# PCIE.net
KiCad netlist of a schematic drawn in EasyEDA Pro
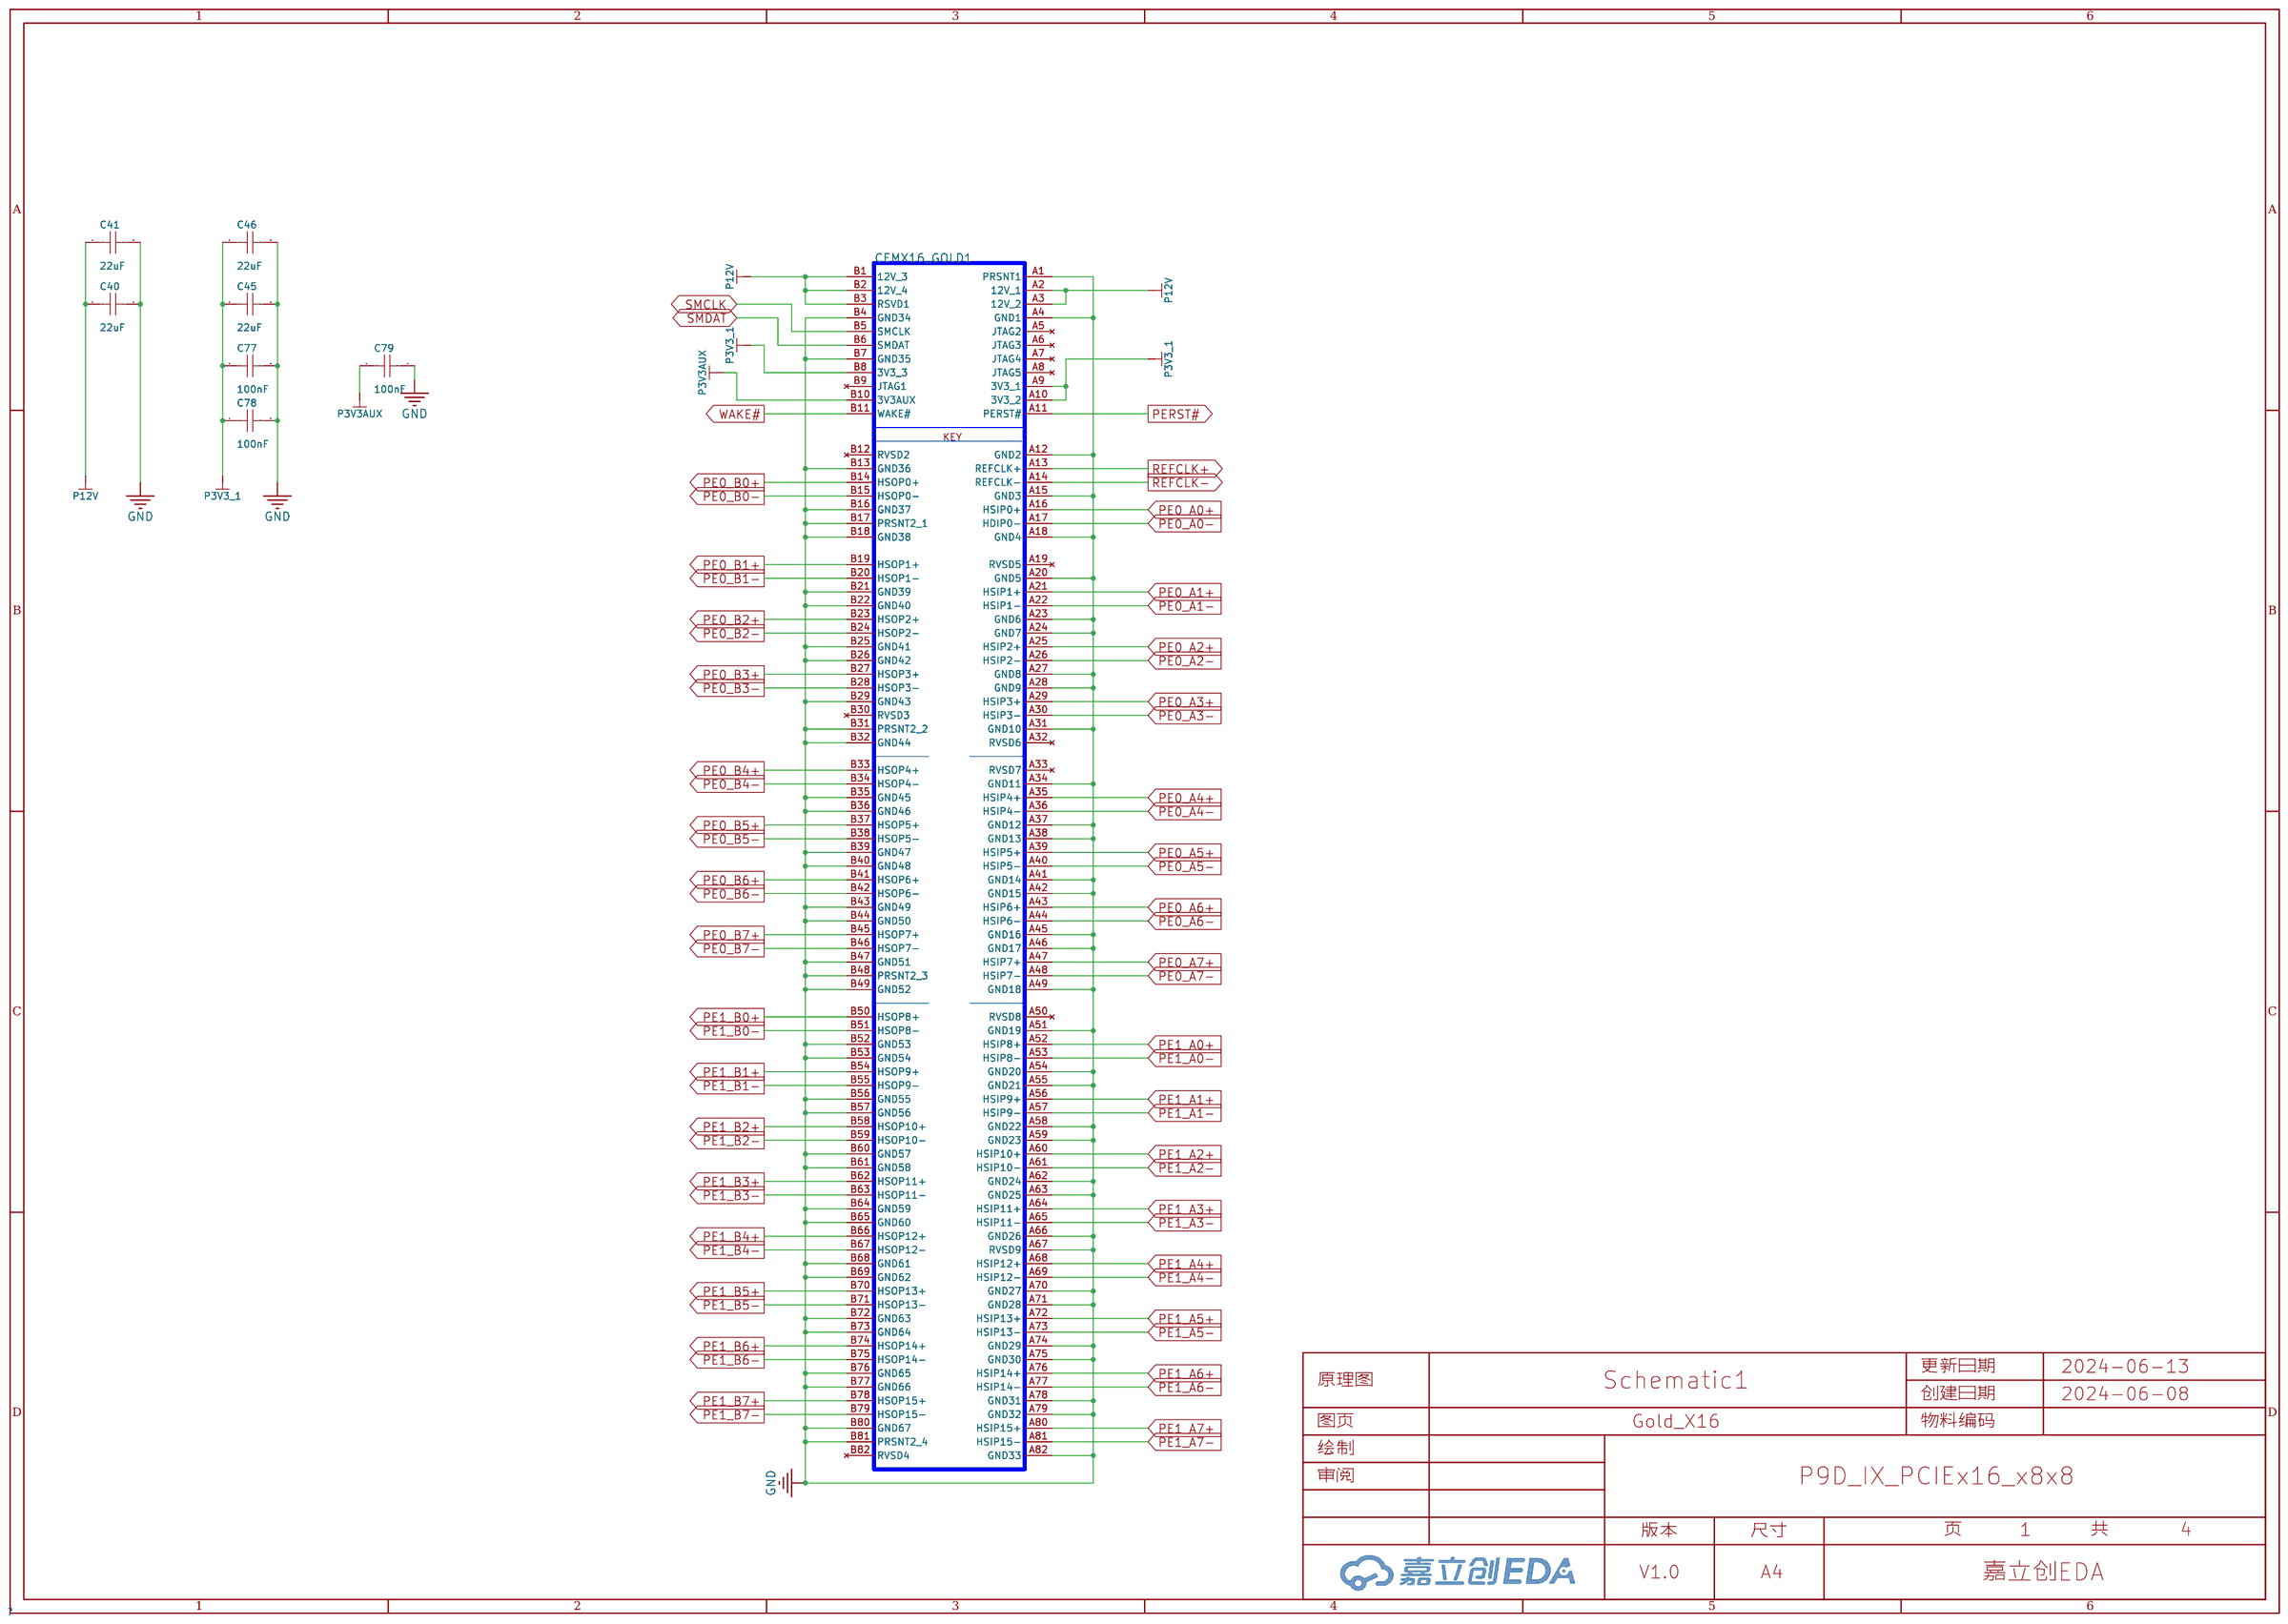
[diagram p0: Gold_X16]
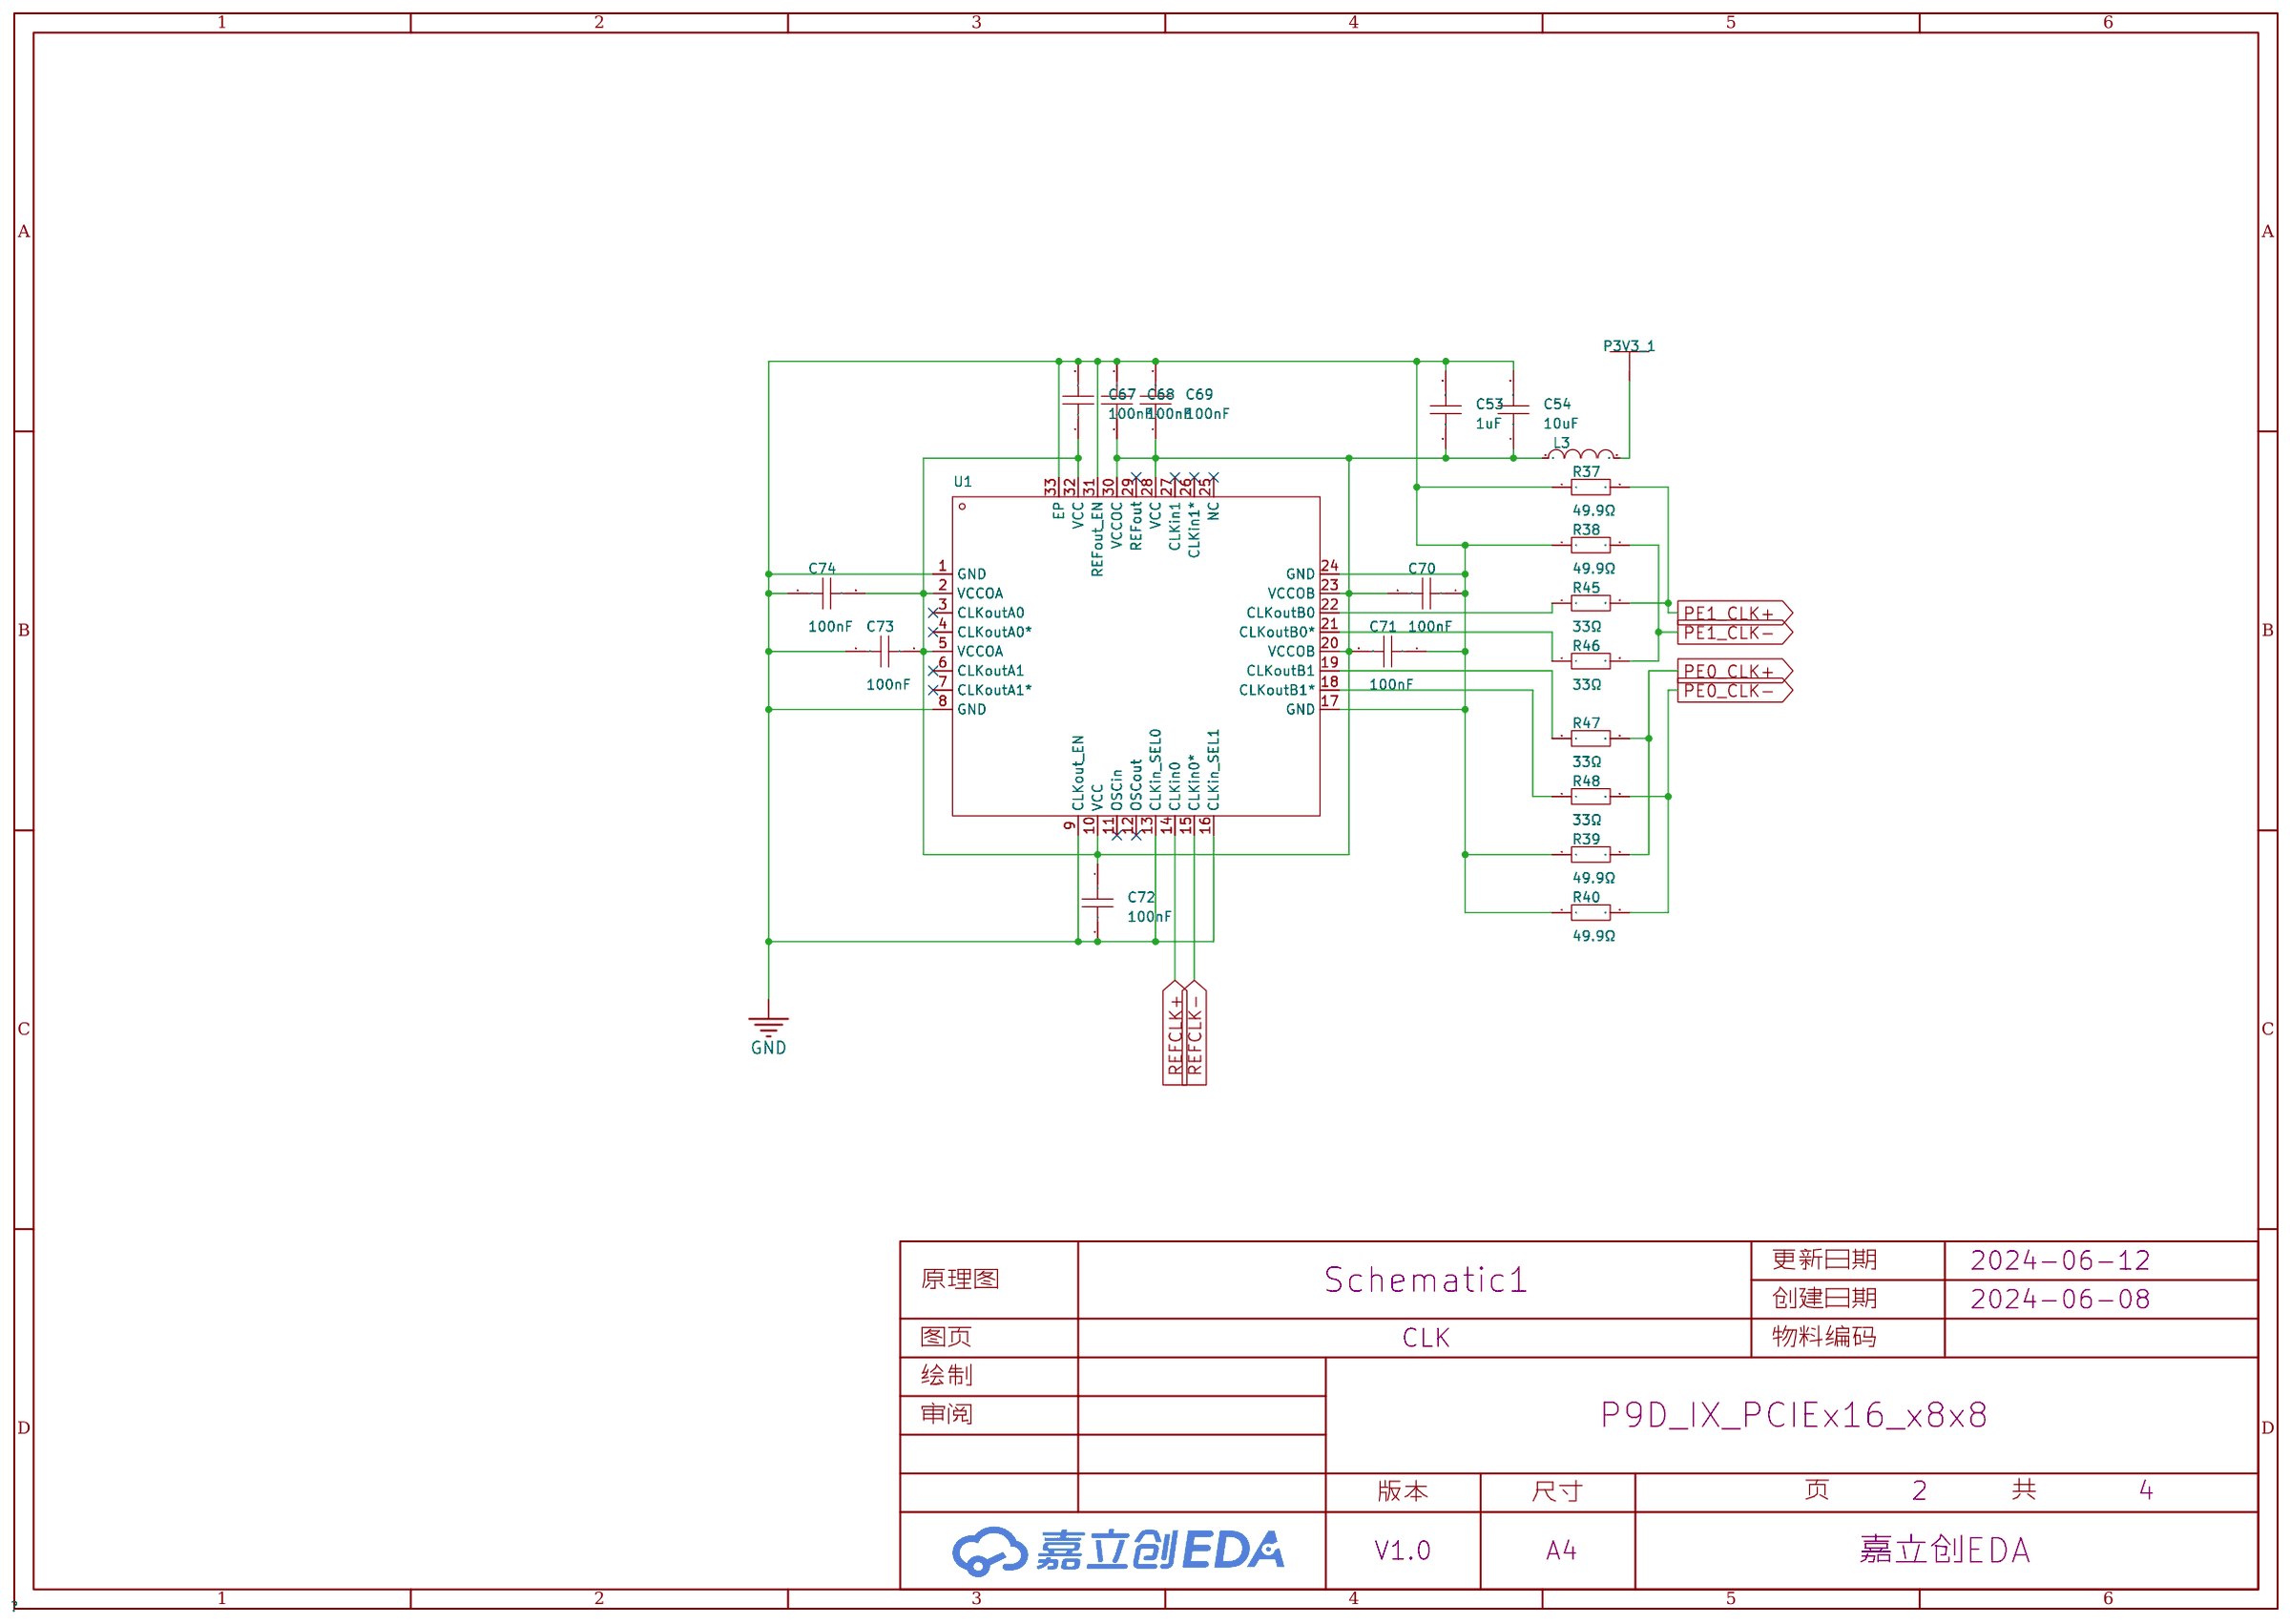
[diagram p1: CLK]
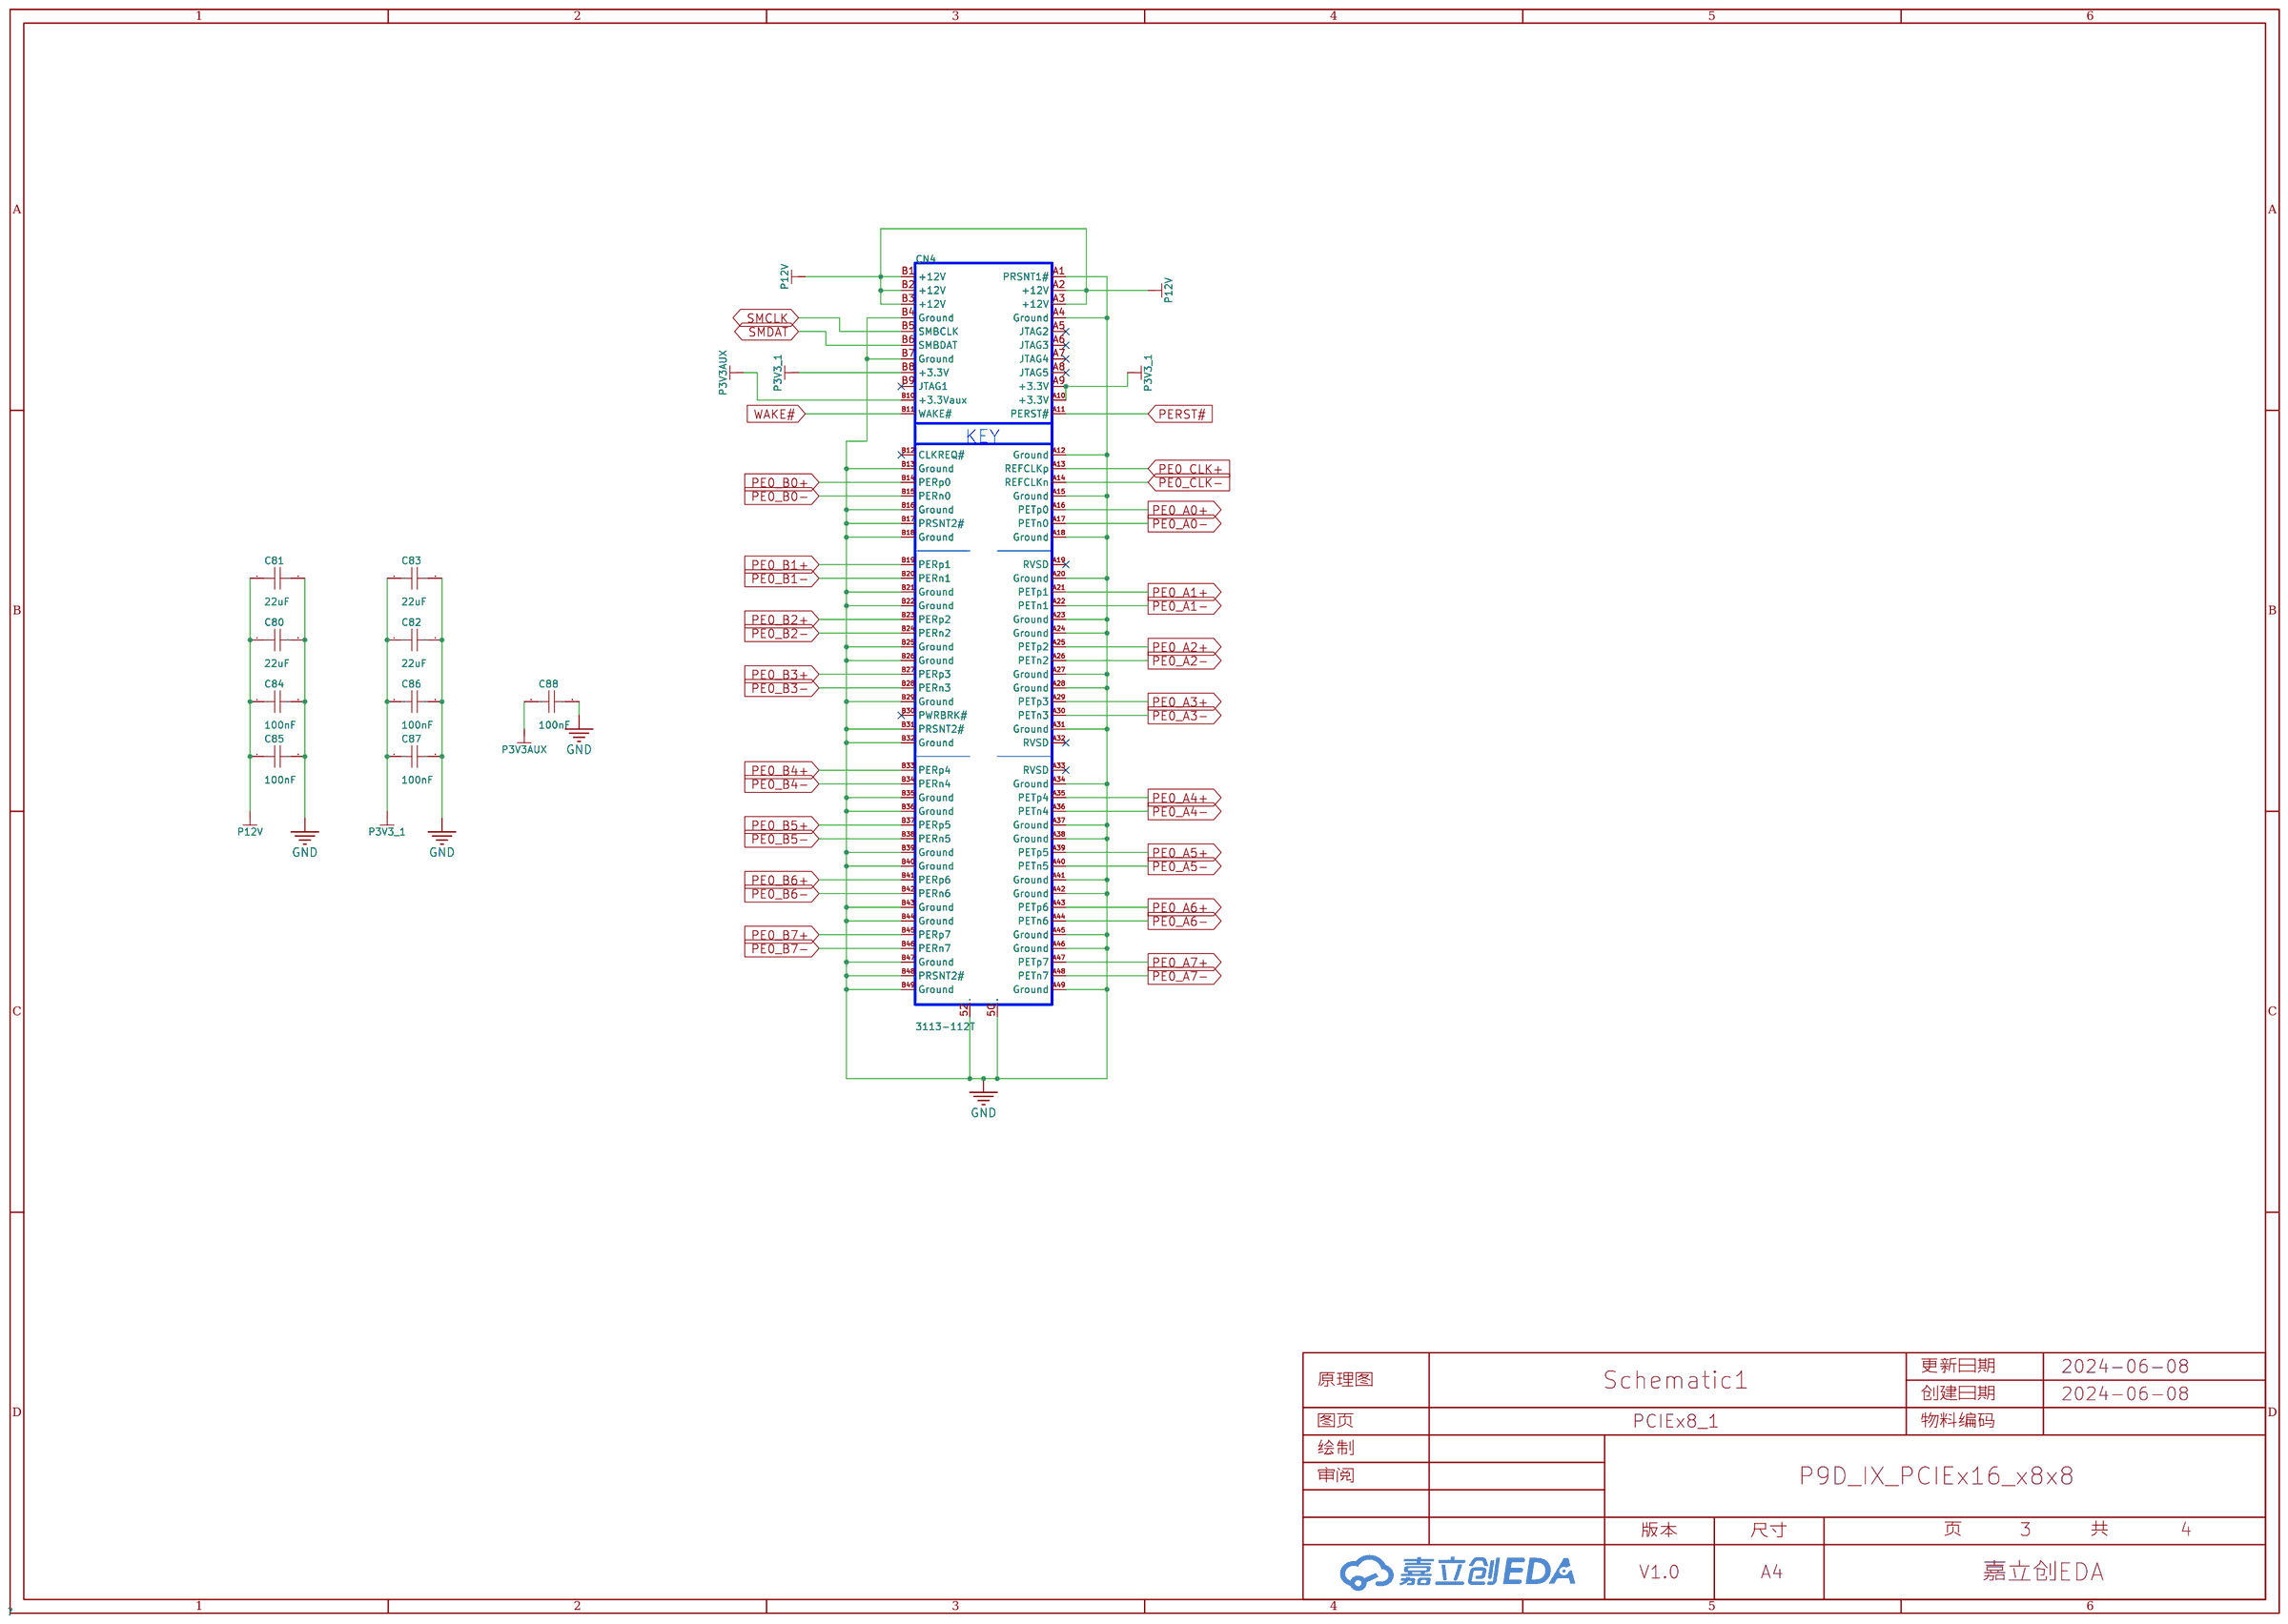
[diagram p2: PCIEx8_1]
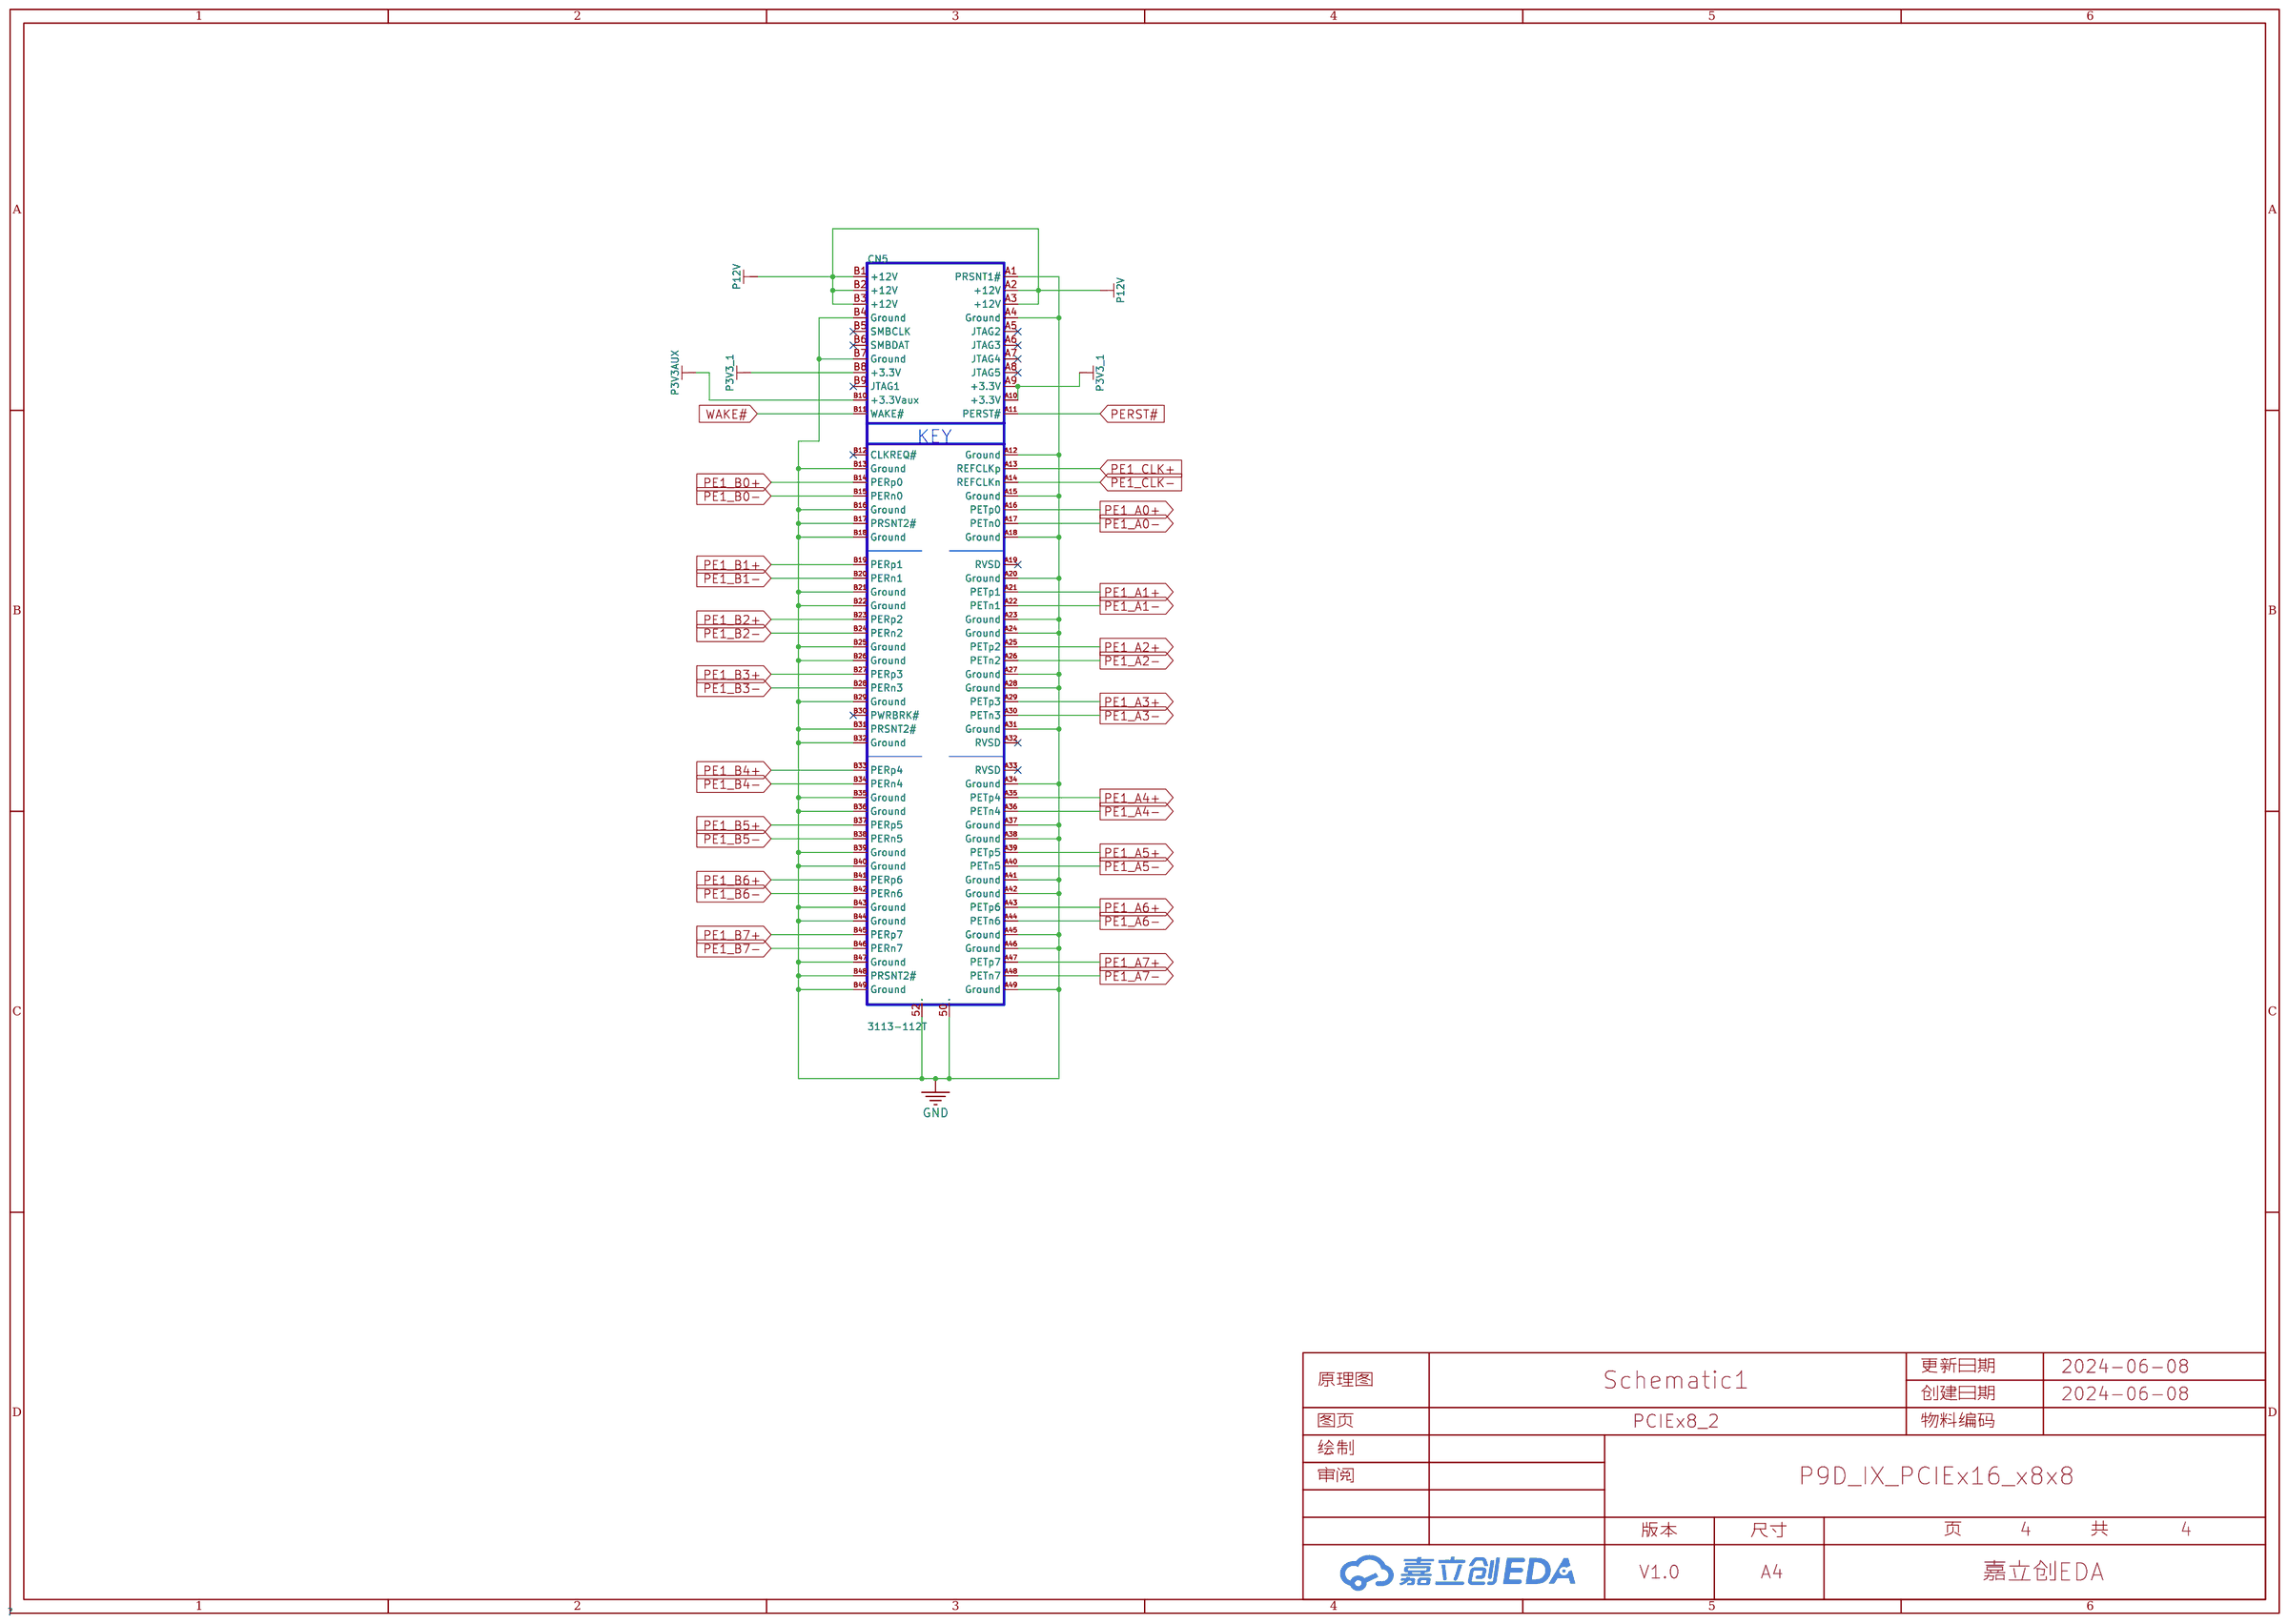
[diagram p3: PCIEx8_2]

(export (version "E")
  (design (tool "Eeschema 10.0.6"))
  (components
    (comp (ref "C40")
      (value "22uF")
      (footprint "easyedapro:C0402")
      (fields
        (field (name "Manufacturer Part") "CL21A226MAQNNNE")
        (field (name "Manufacturer") "SAMSUNG(三星)")
      )
      (libsource (lib "easyedapro") (part "CapAcitance"))
    )
    (comp (ref "C41")
      (value "22uF")
      (footprint "easyedapro:C0402")
      (fields
        (field (name "Manufacturer Part") "CL21A226MAQNNNE")
        (field (name "Manufacturer") "SAMSUNG(三星)")
      )
      (libsource (lib "easyedapro") (part "CapAcitance"))
    )
    (comp (ref "C45")
      (value "22uF")
      (footprint "easyedapro:C0402")
      (fields
        (field (name "Manufacturer Part") "CL21A226MAQNNNE")
        (field (name "Manufacturer") "SAMSUNG(三星)")
      )
      (libsource (lib "easyedapro") (part "CapAcitance"))
    )
    (comp (ref "C46")
      (value "22uF")
      (footprint "easyedapro:C0402")
      (fields
        (field (name "Manufacturer Part") "CL21A226MAQNNNE")
        (field (name "Manufacturer") "SAMSUNG(三星)")
      )
      (libsource (lib "easyedapro") (part "CapAcitance"))
    )
    (comp (ref "C77")
      (value "100nF")
      (footprint "easyedapro:C0402")
      (fields
        (field (name "Manufacturer Part") "CC0603KRX7R9BB104")
        (field (name "Manufacturer") "YAGEO(国巨)")
      )
      (libsource (lib "easyedapro") (part "CapAcitance"))
    )
    (comp (ref "C78")
      (value "100nF")
      (footprint "easyedapro:C0402")
      (fields
        (field (name "Manufacturer Part") "CC0603KRX7R9BB104")
        (field (name "Manufacturer") "YAGEO(国巨)")
      )
      (libsource (lib "easyedapro") (part "CapAcitance"))
    )
    (comp (ref "C79")
      (value "100nF")
      (footprint "easyedapro:C0402")
      (fields
        (field (name "Manufacturer Part") "CC0603KRX7R9BB104")
        (field (name "Manufacturer") "YAGEO(国巨)")
      )
      (libsource (lib "easyedapro") (part "CapAcitance"))
    )
    (comp (ref "CEMX16_GOLD1")
      (value "~")
      (footprint "easyedapro:PCIEX16_GOLD")
      (description "PCIEX16金手指")
      (libsource (lib "easyedapro") (part "PCIEX16金手指"))
    )
    (comp (ref "C53")
      (value "1uF")
      (footprint "easyedapro:C0402")
      (fields
        (field (name "Manufacturer Part") "CL10A105KB8NNNC")
        (field (name "Manufacturer") "SAMSUNG(三星)")
      )
      (libsource (lib "easyedapro") (part "CapAcitance"))
    )
    (comp (ref "C54")
      (value "10uF")
      (footprint "easyedapro:C0402")
      (fields
        (field (name "Manufacturer Part") "CL10A106KP8NNNC")
        (field (name "Manufacturer") "SAMSUNG(三星)")
      )
      (libsource (lib "easyedapro") (part "CapAcitance"))
    )
    (comp (ref "C67")
      (value "100nF")
      (footprint "easyedapro:C0402")
      (fields
        (field (name "Manufacturer Part") "CL05B104KO5NNNC")
        (field (name "Manufacturer") "SAMSUNG(三星)")
      )
      (libsource (lib "easyedapro") (part "CapAcitance"))
    )
    (comp (ref "C68")
      (value "100nF")
      (footprint "easyedapro:C0402")
      (fields
        (field (name "Manufacturer Part") "CL05B104KO5NNNC")
        (field (name "Manufacturer") "SAMSUNG(三星)")
      )
      (libsource (lib "easyedapro") (part "CapAcitance"))
    )
    (comp (ref "C69")
      (value "100nF")
      (footprint "easyedapro:C0402")
      (fields
        (field (name "Manufacturer Part") "CL05B104KO5NNNC")
        (field (name "Manufacturer") "SAMSUNG(三星)")
      )
      (libsource (lib "easyedapro") (part "CapAcitance"))
    )
    (comp (ref "C70")
      (value "100nF")
      (footprint "easyedapro:C0402")
      (fields
        (field (name "Manufacturer Part") "CL05B104KO5NNNC")
        (field (name "Manufacturer") "SAMSUNG(三星)")
      )
      (libsource (lib "easyedapro") (part "CapAcitance"))
    )
    (comp (ref "C71")
      (value "100nF")
      (footprint "easyedapro:C0402")
      (fields
        (field (name "Manufacturer Part") "CL05B104KO5NNNC")
        (field (name "Manufacturer") "SAMSUNG(三星)")
      )
      (libsource (lib "easyedapro") (part "CapAcitance"))
    )
    (comp (ref "C72")
      (value "100nF")
      (footprint "easyedapro:C0402")
      (fields
        (field (name "Manufacturer Part") "CL05B104KO5NNNC")
        (field (name "Manufacturer") "SAMSUNG(三星)")
      )
      (libsource (lib "easyedapro") (part "CapAcitance"))
    )
    (comp (ref "C73")
      (value "100nF")
      (footprint "easyedapro:C0402")
      (fields
        (field (name "Manufacturer Part") "CL05B104KO5NNNC")
        (field (name "Manufacturer") "SAMSUNG(三星)")
      )
      (libsource (lib "easyedapro") (part "CapAcitance"))
    )
    (comp (ref "C74")
      (value "100nF")
      (footprint "easyedapro:C0402")
      (fields
        (field (name "Manufacturer Part") "CL05B104KO5NNNC")
        (field (name "Manufacturer") "SAMSUNG(三星)")
      )
      (libsource (lib "easyedapro") (part "CapAcitance"))
    )
    (comp (ref "L3")
      (value "~")
      (footprint "easyedapro:L0805")
      (description "标称阻抗@测试频率:80Ω@100MHz;误差:±25%;直流电阻(RDC):0.04Ω;额定电流:3000mA;电路数:1;")
      (fields
        (field (name "Manufacturer Part") "PZ2012D800-3R0TF")
        (field (name "Manufacturer") "Sunlord(顺络)")
      )
      (libsource (lib "easyedapro") (part "PZ2012D800-3R0TF"))
    )
    (comp (ref "R37")
      (value "49.9Ω")
      (footprint "easyedapro:R0402")
      (fields (field (name "Manufacturer Part") "ERA2AEB49R9X") (field (name "Manufacturer") "PANASONIC(松下)"))
      (libsource (lib "easyedapro") (part "电阻"))
    )
    (comp (ref "R38")
      (value "49.9Ω")
      (footprint "easyedapro:R0402")
      (fields (field (name "Manufacturer Part") "ERA2AEB49R9X") (field (name "Manufacturer") "PANASONIC(松下)"))
      (libsource (lib "easyedapro") (part "电阻"))
    )
    (comp (ref "R39")
      (value "49.9Ω")
      (footprint "easyedapro:R0402")
      (fields (field (name "Manufacturer Part") "ERA2AEB49R9X") (field (name "Manufacturer") "PANASONIC(松下)"))
      (libsource (lib "easyedapro") (part "电阻"))
    )
    (comp (ref "R40")
      (value "49.9Ω")
      (footprint "easyedapro:R0402")
      (fields (field (name "Manufacturer Part") "ERA2AEB49R9X") (field (name "Manufacturer") "PANASONIC(松下)"))
      (libsource (lib "easyedapro") (part "电阻"))
    )
    (comp (ref "R45")
      (value "33Ω")
      (footprint "easyedapro:R0402")
      (fields (field (name "Manufacturer Part") "RT0402BRD0733RL") (field (name "Manufacturer") "YAGEO(国巨)"))
      (libsource (lib "easyedapro") (part "电阻"))
    )
    (comp (ref "R46")
      (value "33Ω")
      (footprint "easyedapro:R0402")
      (fields (field (name "Manufacturer Part") "RT0402BRD0733RL") (field (name "Manufacturer") "YAGEO(国巨)"))
      (libsource (lib "easyedapro") (part "电阻"))
    )
    (comp (ref "R47")
      (value "33Ω")
      (footprint "easyedapro:R0402")
      (fields (field (name "Manufacturer Part") "RT0402BRD0733RL") (field (name "Manufacturer") "YAGEO(国巨)"))
      (libsource (lib "easyedapro") (part "电阻"))
    )
    (comp (ref "R48")
      (value "33Ω")
      (footprint "easyedapro:R0402")
      (fields (field (name "Manufacturer Part") "RT0402BRD0733RL") (field (name "Manufacturer") "YAGEO(国巨)"))
      (libsource (lib "easyedapro") (part "电阻"))
    )
    (comp (ref "U1")
      (value "~")
      (fields (field (name "Manufacturer Part") "LMK00334RTVR") (field (name "Manufacturer") "TI(德州仪器)"))
      (libsource (lib "easyedapro") (part "lmk00334rtvr"))
    )
    (comp (ref "C80")
      (value "22uF")
      (footprint "easyedapro:C0402")
      (fields
        (field (name "Manufacturer Part") "CL21A226MAQNNNE")
        (field (name "Manufacturer") "SAMSUNG(三星)")
      )
      (libsource (lib "easyedapro") (part "CapAcitance"))
    )
    (comp (ref "C81")
      (value "22uF")
      (footprint "easyedapro:C0402")
      (fields
        (field (name "Manufacturer Part") "CL21A226MAQNNNE")
        (field (name "Manufacturer") "SAMSUNG(三星)")
      )
      (libsource (lib "easyedapro") (part "CapAcitance"))
    )
    (comp (ref "C82")
      (value "22uF")
      (footprint "easyedapro:C0402")
      (fields
        (field (name "Manufacturer Part") "CL21A226MAQNNNE")
        (field (name "Manufacturer") "SAMSUNG(三星)")
      )
      (libsource (lib "easyedapro") (part "CapAcitance"))
    )
    (comp (ref "C83")
      (value "22uF")
      (footprint "easyedapro:C0402")
      (fields
        (field (name "Manufacturer Part") "CL21A226MAQNNNE")
        (field (name "Manufacturer") "SAMSUNG(三星)")
      )
      (libsource (lib "easyedapro") (part "CapAcitance"))
    )
    (comp (ref "C84")
      (value "100nF")
      (footprint "easyedapro:C0402")
      (fields
        (field (name "Manufacturer Part") "CC0603KRX7R9BB104")
        (field (name "Manufacturer") "YAGEO(国巨)")
      )
      (libsource (lib "easyedapro") (part "CapAcitance"))
    )
    (comp (ref "C85")
      (value "100nF")
      (footprint "easyedapro:C0402")
      (fields
        (field (name "Manufacturer Part") "CC0603KRX7R9BB104")
        (field (name "Manufacturer") "YAGEO(国巨)")
      )
      (libsource (lib "easyedapro") (part "CapAcitance"))
    )
    (comp (ref "C86")
      (value "100nF")
      (footprint "easyedapro:C0402")
      (fields
        (field (name "Manufacturer Part") "CC0603KRX7R9BB104")
        (field (name "Manufacturer") "YAGEO(国巨)")
      )
      (libsource (lib "easyedapro") (part "CapAcitance"))
    )
    (comp (ref "C87")
      (value "100nF")
      (footprint "easyedapro:C0402")
      (fields
        (field (name "Manufacturer Part") "CC0603KRX7R9BB104")
        (field (name "Manufacturer") "YAGEO(国巨)")
      )
      (libsource (lib "easyedapro") (part "CapAcitance"))
    )
    (comp (ref "C88")
      (value "100nF")
      (footprint "easyedapro:C0402")
      (fields
        (field (name "Manufacturer Part") "CC0603KRX7R9BB104")
        (field (name "Manufacturer") "YAGEO(国巨)")
      )
      (libsource (lib "easyedapro") (part "CapAcitance"))
    )
    (comp (ref "CN4")
      (value "3113-112T")
      (footprint "easyedapro:CONN-SMD_98P-P1.00-V_3133")
      (description "连接器类型:PCI-E;间距:1mm;引脚总数:98P;安装方式:立贴;工作温度范围:-40°C~+85°C;")
      (fields (field (name "Manufacturer") "UMaxconn(友贸)"))
      (libsource (lib "easyedapro") (part "PCIE_X8"))
    )
    (comp (ref "CN5")
      (value "3113-112T")
      (footprint "easyedapro:CONN-SMD_98P-P1.00-V_3133")
      (description "连接器类型:PCI-E;间距:1mm;引脚总数:98P;安装方式:立贴;工作温度范围:-40°C~+85°C;")
      (fields (field (name "Manufacturer") "UMaxconn(友贸)"))
      (libsource (lib "easyedapro") (part "PCIE_X8"))
    )
  )
  (nets
    (net (code "1") (name "GND") (class "Default")
      (node (ref "C40") (pin "2") (pinfunction "2_2") (pintype "input"))
      (node (ref "C41") (pin "2") (pinfunction "2_2") (pintype "input"))
      (node (ref "C45") (pin "2") (pinfunction "2_2") (pintype "input"))
      (node (ref "C46") (pin "2") (pinfunction "2_2") (pintype "input"))
      (node (ref "C53") (pin "2") (pinfunction "2_2") (pintype "input"))
      (node (ref "C54") (pin "2") (pinfunction "2_2") (pintype "input"))
      (node (ref "C67") (pin "2") (pinfunction "2_2") (pintype "input"))
      (node (ref "C68") (pin "2") (pinfunction "2_2") (pintype "input"))
      (node (ref "C69") (pin "2") (pinfunction "2_2") (pintype "input"))
      (node (ref "C70") (pin "1") (pinfunction "1_1") (pintype "input"))
      (node (ref "C71") (pin "1") (pinfunction "1_1") (pintype "input"))
      (node (ref "C72") (pin "2") (pinfunction "2_2") (pintype "input"))
      (node (ref "C73") (pin "1") (pinfunction "1_1") (pintype "input"))
      (node (ref "C74") (pin "1") (pinfunction "1_1") (pintype "input"))
      (node (ref "C77") (pin "2") (pinfunction "2_2") (pintype "input"))
      (node (ref "C78") (pin "2") (pinfunction "2_2") (pintype "input"))
      (node (ref "C79") (pin "2") (pinfunction "2_2") (pintype "input"))
      (node (ref "C80") (pin "2") (pinfunction "2_2") (pintype "input"))
      (node (ref "C81") (pin "2") (pinfunction "2_2") (pintype "input"))
      (node (ref "C82") (pin "2") (pinfunction "2_2") (pintype "input"))
      (node (ref "C83") (pin "2") (pinfunction "2_2") (pintype "input"))
      (node (ref "C84") (pin "2") (pinfunction "2_2") (pintype "input"))
      (node (ref "C85") (pin "2") (pinfunction "2_2") (pintype "input"))
      (node (ref "C86") (pin "2") (pinfunction "2_2") (pintype "input"))
      (node (ref "C87") (pin "2") (pinfunction "2_2") (pintype "input"))
      (node (ref "C88") (pin "2") (pinfunction "2_2") (pintype "input"))
      (node (ref "CEMX16_GOLD1") (pin "A1") (pinfunction "PRSNT1_A1") (pintype "input"))
      (node (ref "CEMX16_GOLD1") (pin "A12") (pinfunction "GND2_A12") (pintype "bidirectional"))
      (node (ref "CEMX16_GOLD1") (pin "A15") (pinfunction "GND3_A15") (pintype "bidirectional"))
      (node (ref "CEMX16_GOLD1") (pin "A18") (pinfunction "GND4_A18") (pintype "bidirectional"))
      (node (ref "CEMX16_GOLD1") (pin "A20") (pinfunction "GND5_A20") (pintype "bidirectional"))
      (node (ref "CEMX16_GOLD1") (pin "A23") (pinfunction "GND6_A23") (pintype "bidirectional"))
      (node (ref "CEMX16_GOLD1") (pin "A24") (pinfunction "GND7_A24") (pintype "bidirectional"))
      (node (ref "CEMX16_GOLD1") (pin "A27") (pinfunction "GND8_A27") (pintype "bidirectional"))
      (node (ref "CEMX16_GOLD1") (pin "A28") (pinfunction "GND9_A28") (pintype "bidirectional"))
      (node (ref "CEMX16_GOLD1") (pin "A31") (pinfunction "GND10_A31") (pintype "bidirectional"))
      (node (ref "CEMX16_GOLD1") (pin "A34") (pinfunction "GND11_A34") (pintype "bidirectional"))
      (node (ref "CEMX16_GOLD1") (pin "A37") (pinfunction "GND12_A37") (pintype "bidirectional"))
      (node (ref "CEMX16_GOLD1") (pin "A38") (pinfunction "GND13_A38") (pintype "bidirectional"))
      (node (ref "CEMX16_GOLD1") (pin "A4") (pinfunction "GND1_A4") (pintype "bidirectional"))
      (node (ref "CEMX16_GOLD1") (pin "A41") (pinfunction "GND14_A41") (pintype "bidirectional"))
      (node (ref "CEMX16_GOLD1") (pin "A42") (pinfunction "GND15_A42") (pintype "bidirectional"))
      (node (ref "CEMX16_GOLD1") (pin "A45") (pinfunction "GND16_A45") (pintype "bidirectional"))
      (node (ref "CEMX16_GOLD1") (pin "A46") (pinfunction "GND17_A46") (pintype "bidirectional"))
      (node (ref "CEMX16_GOLD1") (pin "A49") (pinfunction "GND18_A49") (pintype "bidirectional"))
      (node (ref "CEMX16_GOLD1") (pin "A51") (pinfunction "GND19_A51") (pintype "bidirectional"))
      (node (ref "CEMX16_GOLD1") (pin "A54") (pinfunction "GND20_A54") (pintype "bidirectional"))
      (node (ref "CEMX16_GOLD1") (pin "A55") (pinfunction "GND21_A55") (pintype "bidirectional"))
      (node (ref "CEMX16_GOLD1") (pin "A58") (pinfunction "GND22_A58") (pintype "bidirectional"))
      (node (ref "CEMX16_GOLD1") (pin "A59") (pinfunction "GND23_A59") (pintype "bidirectional"))
      (node (ref "CEMX16_GOLD1") (pin "A62") (pinfunction "GND24_A62") (pintype "bidirectional"))
      (node (ref "CEMX16_GOLD1") (pin "A63") (pinfunction "GND25_A63") (pintype "bidirectional"))
      (node (ref "CEMX16_GOLD1") (pin "A66") (pinfunction "GND26_A66") (pintype "bidirectional"))
      (node (ref "CEMX16_GOLD1") (pin "A67") (pinfunction "RVSD9_A67") (pintype "input"))
      (node (ref "CEMX16_GOLD1") (pin "A70") (pinfunction "GND27_A70") (pintype "bidirectional"))
      (node (ref "CEMX16_GOLD1") (pin "A71") (pinfunction "GND28_A71") (pintype "bidirectional"))
      (node (ref "CEMX16_GOLD1") (pin "A74") (pinfunction "GND29_A74") (pintype "bidirectional"))
      (node (ref "CEMX16_GOLD1") (pin "A75") (pinfunction "GND30_A75") (pintype "bidirectional"))
      (node (ref "CEMX16_GOLD1") (pin "A78") (pinfunction "GND31_A78") (pintype "bidirectional"))
      (node (ref "CEMX16_GOLD1") (pin "A79") (pinfunction "GND32_A79") (pintype "bidirectional"))
      (node (ref "CEMX16_GOLD1") (pin "A82") (pinfunction "GND33_A82") (pintype "bidirectional"))
      (node (ref "CEMX16_GOLD1") (pin "B13") (pinfunction "GND36_B13") (pintype "bidirectional"))
      (node (ref "CEMX16_GOLD1") (pin "B16") (pinfunction "GND37_B16") (pintype "bidirectional"))
      (node (ref "CEMX16_GOLD1") (pin "B17") (pinfunction "PRSNT2_1_B17") (pintype "input"))
      (node (ref "CEMX16_GOLD1") (pin "B18") (pinfunction "GND38_B18") (pintype "bidirectional"))
      (node (ref "CEMX16_GOLD1") (pin "B21") (pinfunction "GND39_B21") (pintype "bidirectional"))
      (node (ref "CEMX16_GOLD1") (pin "B22") (pinfunction "GND40_B22") (pintype "bidirectional"))
      (node (ref "CEMX16_GOLD1") (pin "B25") (pinfunction "GND41_B25") (pintype "bidirectional"))
      (node (ref "CEMX16_GOLD1") (pin "B26") (pinfunction "GND42_B26") (pintype "bidirectional"))
      (node (ref "CEMX16_GOLD1") (pin "B29") (pinfunction "GND43_B29") (pintype "bidirectional"))
      (node (ref "CEMX16_GOLD1") (pin "B31") (pinfunction "PRSNT2_2_B31") (pintype "input"))
      (node (ref "CEMX16_GOLD1") (pin "B32") (pinfunction "GND44_B32") (pintype "bidirectional"))
      (node (ref "CEMX16_GOLD1") (pin "B35") (pinfunction "GND45_B35") (pintype "bidirectional"))
      (node (ref "CEMX16_GOLD1") (pin "B36") (pinfunction "GND46_B36") (pintype "bidirectional"))
      (node (ref "CEMX16_GOLD1") (pin "B39") (pinfunction "GND47_B39") (pintype "bidirectional"))
      (node (ref "CEMX16_GOLD1") (pin "B4") (pinfunction "GND34_B4") (pintype "bidirectional"))
      (node (ref "CEMX16_GOLD1") (pin "B40") (pinfunction "GND48_B40") (pintype "bidirectional"))
      (node (ref "CEMX16_GOLD1") (pin "B43") (pinfunction "GND49_B43") (pintype "bidirectional"))
      (node (ref "CEMX16_GOLD1") (pin "B44") (pinfunction "GND50_B44") (pintype "bidirectional"))
      (node (ref "CEMX16_GOLD1") (pin "B47") (pinfunction "GND51_B47") (pintype "bidirectional"))
      (node (ref "CEMX16_GOLD1") (pin "B48") (pinfunction "PRSNT2_3_B48") (pintype "input"))
      (node (ref "CEMX16_GOLD1") (pin "B49") (pinfunction "GND52_B49") (pintype "bidirectional"))
      (node (ref "CEMX16_GOLD1") (pin "B52") (pinfunction "GND53_B52") (pintype "bidirectional"))
      (node (ref "CEMX16_GOLD1") (pin "B53") (pinfunction "GND54_B53") (pintype "bidirectional"))
      (node (ref "CEMX16_GOLD1") (pin "B56") (pinfunction "GND55_B56") (pintype "bidirectional"))
      (node (ref "CEMX16_GOLD1") (pin "B57") (pinfunction "GND56_B57") (pintype "bidirectional"))
      (node (ref "CEMX16_GOLD1") (pin "B60") (pinfunction "GND57_B60") (pintype "bidirectional"))
      (node (ref "CEMX16_GOLD1") (pin "B61") (pinfunction "GND58_B61") (pintype "bidirectional"))
      (node (ref "CEMX16_GOLD1") (pin "B64") (pinfunction "GND59_B64") (pintype "bidirectional"))
      (node (ref "CEMX16_GOLD1") (pin "B65") (pinfunction "GND60_B65") (pintype "bidirectional"))
      (node (ref "CEMX16_GOLD1") (pin "B68") (pinfunction "GND61_B68") (pintype "bidirectional"))
      (node (ref "CEMX16_GOLD1") (pin "B69") (pinfunction "GND62_B69") (pintype "bidirectional"))
      (node (ref "CEMX16_GOLD1") (pin "B7") (pinfunction "GND35_B7") (pintype "bidirectional"))
      (node (ref "CEMX16_GOLD1") (pin "B72") (pinfunction "GND63_B72") (pintype "bidirectional"))
      (node (ref "CEMX16_GOLD1") (pin "B73") (pinfunction "GND64_B73") (pintype "bidirectional"))
      (node (ref "CEMX16_GOLD1") (pin "B76") (pinfunction "GND65_B76") (pintype "bidirectional"))
      (node (ref "CEMX16_GOLD1") (pin "B77") (pinfunction "GND66_B77") (pintype "bidirectional"))
      (node (ref "CEMX16_GOLD1") (pin "B80") (pinfunction "GND67_B80") (pintype "bidirectional"))
      (node (ref "CEMX16_GOLD1") (pin "B81") (pinfunction "PRSNT2_4_B81") (pintype "input"))
      (node (ref "CN4") (pin "50") (pinfunction "GND_50") (pintype "output"))
      (node (ref "CN4") (pin "52") (pinfunction "GND_52") (pintype "output"))
      (node (ref "CN4") (pin "A1") (pinfunction "PRSNT1#_A1") (pintype "input"))
      (node (ref "CN4") (pin "A12") (pinfunction "Ground_A12") (pintype "bidirectional"))
      (node (ref "CN4") (pin "A15") (pinfunction "Ground_A15") (pintype "bidirectional"))
      (node (ref "CN4") (pin "A18") (pinfunction "Ground_A18") (pintype "bidirectional"))
      (node (ref "CN4") (pin "A20") (pinfunction "Ground_A20") (pintype "bidirectional"))
      (node (ref "CN4") (pin "A23") (pinfunction "Ground_A23") (pintype "bidirectional"))
      (node (ref "CN4") (pin "A24") (pinfunction "Ground_A24") (pintype "bidirectional"))
      (node (ref "CN4") (pin "A27") (pinfunction "Ground_A27") (pintype "bidirectional"))
      (node (ref "CN4") (pin "A28") (pinfunction "Ground_A28") (pintype "bidirectional"))
      (node (ref "CN4") (pin "A31") (pinfunction "Ground_A31") (pintype "bidirectional"))
      (node (ref "CN4") (pin "A34") (pinfunction "Ground_A34") (pintype "bidirectional"))
      (node (ref "CN4") (pin "A37") (pinfunction "Ground_A37") (pintype "bidirectional"))
      (node (ref "CN4") (pin "A38") (pinfunction "Ground_A38") (pintype "bidirectional"))
      (node (ref "CN4") (pin "A4") (pinfunction "Ground_A4") (pintype "bidirectional"))
      (node (ref "CN4") (pin "A41") (pinfunction "Ground_A41") (pintype "bidirectional"))
      (node (ref "CN4") (pin "A42") (pinfunction "Ground_A42") (pintype "bidirectional"))
      (node (ref "CN4") (pin "A45") (pinfunction "Ground_A45") (pintype "bidirectional"))
      (node (ref "CN4") (pin "A46") (pinfunction "Ground_A46") (pintype "bidirectional"))
      (node (ref "CN4") (pin "A49") (pinfunction "Ground_A49") (pintype "bidirectional"))
      (node (ref "CN4") (pin "B13") (pinfunction "Ground_B13") (pintype "bidirectional"))
      (node (ref "CN4") (pin "B16") (pinfunction "Ground_B16") (pintype "bidirectional"))
      (node (ref "CN4") (pin "B17") (pinfunction "PRSNT2#_B17") (pintype "input"))
      (node (ref "CN4") (pin "B18") (pinfunction "Ground_B18") (pintype "bidirectional"))
      (node (ref "CN4") (pin "B21") (pinfunction "Ground_B21") (pintype "bidirectional"))
      (node (ref "CN4") (pin "B22") (pinfunction "Ground_B22") (pintype "bidirectional"))
      (node (ref "CN4") (pin "B25") (pinfunction "Ground_B25") (pintype "bidirectional"))
      (node (ref "CN4") (pin "B26") (pinfunction "Ground_B26") (pintype "bidirectional"))
      (node (ref "CN4") (pin "B29") (pinfunction "Ground_B29") (pintype "bidirectional"))
      (node (ref "CN4") (pin "B31") (pinfunction "PRSNT2#_B31") (pintype "input"))
      (node (ref "CN4") (pin "B32") (pinfunction "Ground_B32") (pintype "bidirectional"))
      (node (ref "CN4") (pin "B35") (pinfunction "Ground_B35") (pintype "bidirectional"))
      (node (ref "CN4") (pin "B36") (pinfunction "Ground_B36") (pintype "bidirectional"))
      (node (ref "CN4") (pin "B39") (pinfunction "Ground_B39") (pintype "bidirectional"))
      (node (ref "CN4") (pin "B4") (pinfunction "Ground_B4") (pintype "bidirectional"))
      (node (ref "CN4") (pin "B40") (pinfunction "Ground_B40") (pintype "bidirectional"))
      (node (ref "CN4") (pin "B43") (pinfunction "Ground_B43") (pintype "bidirectional"))
      (node (ref "CN4") (pin "B44") (pinfunction "Ground_B44") (pintype "bidirectional"))
      (node (ref "CN4") (pin "B47") (pinfunction "Ground_B47") (pintype "bidirectional"))
      (node (ref "CN4") (pin "B48") (pinfunction "PRSNT2#_B48") (pintype "input"))
      (node (ref "CN4") (pin "B49") (pinfunction "Ground_B49") (pintype "bidirectional"))
      (node (ref "CN4") (pin "B7") (pinfunction "Ground_B7") (pintype "bidirectional"))
      (node (ref "CN5") (pin "50") (pinfunction "GND_50") (pintype "output"))
      (node (ref "CN5") (pin "52") (pinfunction "GND_52") (pintype "output"))
      (node (ref "CN5") (pin "A1") (pinfunction "PRSNT1#_A1") (pintype "input"))
      (node (ref "CN5") (pin "A12") (pinfunction "Ground_A12") (pintype "bidirectional"))
      (node (ref "CN5") (pin "A15") (pinfunction "Ground_A15") (pintype "bidirectional"))
      (node (ref "CN5") (pin "A18") (pinfunction "Ground_A18") (pintype "bidirectional"))
      (node (ref "CN5") (pin "A20") (pinfunction "Ground_A20") (pintype "bidirectional"))
      (node (ref "CN5") (pin "A23") (pinfunction "Ground_A23") (pintype "bidirectional"))
      (node (ref "CN5") (pin "A24") (pinfunction "Ground_A24") (pintype "bidirectional"))
      (node (ref "CN5") (pin "A27") (pinfunction "Ground_A27") (pintype "bidirectional"))
      (node (ref "CN5") (pin "A28") (pinfunction "Ground_A28") (pintype "bidirectional"))
      (node (ref "CN5") (pin "A31") (pinfunction "Ground_A31") (pintype "bidirectional"))
      (node (ref "CN5") (pin "A34") (pinfunction "Ground_A34") (pintype "bidirectional"))
      (node (ref "CN5") (pin "A37") (pinfunction "Ground_A37") (pintype "bidirectional"))
      (node (ref "CN5") (pin "A38") (pinfunction "Ground_A38") (pintype "bidirectional"))
      (node (ref "CN5") (pin "A4") (pinfunction "Ground_A4") (pintype "bidirectional"))
      (node (ref "CN5") (pin "A41") (pinfunction "Ground_A41") (pintype "bidirectional"))
      (node (ref "CN5") (pin "A42") (pinfunction "Ground_A42") (pintype "bidirectional"))
      (node (ref "CN5") (pin "A45") (pinfunction "Ground_A45") (pintype "bidirectional"))
      (node (ref "CN5") (pin "A46") (pinfunction "Ground_A46") (pintype "bidirectional"))
      (node (ref "CN5") (pin "A49") (pinfunction "Ground_A49") (pintype "bidirectional"))
      (node (ref "CN5") (pin "B13") (pinfunction "Ground_B13") (pintype "bidirectional"))
      (node (ref "CN5") (pin "B16") (pinfunction "Ground_B16") (pintype "bidirectional"))
      (node (ref "CN5") (pin "B17") (pinfunction "PRSNT2#_B17") (pintype "input"))
      (node (ref "CN5") (pin "B18") (pinfunction "Ground_B18") (pintype "bidirectional"))
      (node (ref "CN5") (pin "B21") (pinfunction "Ground_B21") (pintype "bidirectional"))
      (node (ref "CN5") (pin "B22") (pinfunction "Ground_B22") (pintype "bidirectional"))
      (node (ref "CN5") (pin "B25") (pinfunction "Ground_B25") (pintype "bidirectional"))
      (node (ref "CN5") (pin "B26") (pinfunction "Ground_B26") (pintype "bidirectional"))
      (node (ref "CN5") (pin "B29") (pinfunction "Ground_B29") (pintype "bidirectional"))
      (node (ref "CN5") (pin "B31") (pinfunction "PRSNT2#_B31") (pintype "input"))
      (node (ref "CN5") (pin "B32") (pinfunction "Ground_B32") (pintype "bidirectional"))
      (node (ref "CN5") (pin "B35") (pinfunction "Ground_B35") (pintype "bidirectional"))
      (node (ref "CN5") (pin "B36") (pinfunction "Ground_B36") (pintype "bidirectional"))
      (node (ref "CN5") (pin "B39") (pinfunction "Ground_B39") (pintype "bidirectional"))
      (node (ref "CN5") (pin "B4") (pinfunction "Ground_B4") (pintype "bidirectional"))
      (node (ref "CN5") (pin "B40") (pinfunction "Ground_B40") (pintype "bidirectional"))
      (node (ref "CN5") (pin "B43") (pinfunction "Ground_B43") (pintype "bidirectional"))
      (node (ref "CN5") (pin "B44") (pinfunction "Ground_B44") (pintype "bidirectional"))
      (node (ref "CN5") (pin "B47") (pinfunction "Ground_B47") (pintype "bidirectional"))
      (node (ref "CN5") (pin "B48") (pinfunction "PRSNT2#_B48") (pintype "input"))
      (node (ref "CN5") (pin "B49") (pinfunction "Ground_B49") (pintype "bidirectional"))
      (node (ref "CN5") (pin "B7") (pinfunction "Ground_B7") (pintype "bidirectional"))
      (node (ref "R37") (pin "1") (pinfunction "1_1") (pintype "input"))
      (node (ref "R38") (pin "1") (pinfunction "1_1") (pintype "input"))
      (node (ref "R39") (pin "1") (pinfunction "1_1") (pintype "input"))
      (node (ref "R40") (pin "1") (pinfunction "1_1") (pintype "input"))
      (node (ref "U1") (pin "1") (pinfunction "GND_1") (pintype "input"))
      (node (ref "U1") (pin "13") (pinfunction "CLKin_SEL0_13") (pintype "input"))
      (node (ref "U1") (pin "16") (pinfunction "CLKin_SEL1_16") (pintype "input"))
      (node (ref "U1") (pin "17") (pinfunction "GND_17") (pintype "input"))
      (node (ref "U1") (pin "24") (pinfunction "GND_24") (pintype "input"))
      (node (ref "U1") (pin "31") (pinfunction "REFout_EN_31") (pintype "input"))
      (node (ref "U1") (pin "33") (pinfunction "EP_33") (pintype "input"))
      (node (ref "U1") (pin "8") (pinfunction "GND_8") (pintype "input"))
      (node (ref "U1") (pin "9") (pinfunction "CLKout_EN_9") (pintype "input"))
    )
    (net (code "2") (name "Net-(U1-CLKoutB0)") (class "Default")
      (node (ref "R45") (pin "1") (pinfunction "1_1") (pintype "input"))
      (node (ref "U1") (pin "22") (pinfunction "CLKoutB0_22") (pintype "input"))
    )
    (net (code "3") (name "Net-(U1-CLKoutB0*)") (class "Default")
      (node (ref "R46") (pin "1") (pinfunction "1_1") (pintype "input"))
      (node (ref "U1") (pin "21") (pinfunction "CLKoutB0*_21") (pintype "input"))
    )
    (net (code "4") (name "Net-(U1-CLKoutB1)") (class "Default")
      (node (ref "R47") (pin "1") (pinfunction "1_1") (pintype "input"))
      (node (ref "U1") (pin "19") (pinfunction "CLKoutB1_19") (pintype "input"))
    )
    (net (code "5") (name "Net-(U1-CLKoutB1*)") (class "Default")
      (node (ref "R48") (pin "1") (pinfunction "1_1") (pintype "input"))
      (node (ref "U1") (pin "18") (pinfunction "CLKoutB1*_18") (pintype "input"))
    )
    (net (code "6") (name "Net-(U1-VCCOC)") (class "Default")
      (node (ref "C53") (pin "1") (pinfunction "1_1") (pintype "input"))
      (node (ref "C54") (pin "1") (pinfunction "1_1") (pintype "input"))
      (node (ref "C67") (pin "1") (pinfunction "1_1") (pintype "input"))
      (node (ref "C68") (pin "1") (pinfunction "1_1") (pintype "input"))
      (node (ref "C69") (pin "1") (pinfunction "1_1") (pintype "input"))
      (node (ref "C70") (pin "2") (pinfunction "2_2") (pintype "input"))
      (node (ref "C71") (pin "2") (pinfunction "2_2") (pintype "input"))
      (node (ref "C72") (pin "1") (pinfunction "1_1") (pintype "input"))
      (node (ref "C73") (pin "2") (pinfunction "2_2") (pintype "input"))
      (node (ref "C74") (pin "2") (pinfunction "2_2") (pintype "input"))
      (node (ref "L3") (pin "1") (pinfunction "1_1") (pintype "input"))
      (node (ref "U1") (pin "10") (pinfunction "VCC_10") (pintype "input"))
      (node (ref "U1") (pin "2") (pinfunction "VCCOA_2") (pintype "input"))
      (node (ref "U1") (pin "20") (pinfunction "VCCOB_20") (pintype "input"))
      (node (ref "U1") (pin "23") (pinfunction "VCCOB_23") (pintype "input"))
      (node (ref "U1") (pin "28") (pinfunction "VCC_28") (pintype "input"))
      (node (ref "U1") (pin "30") (pinfunction "VCCOC_30") (pintype "input"))
      (node (ref "U1") (pin "32") (pinfunction "VCC_32") (pintype "input"))
      (node (ref "U1") (pin "5") (pinfunction "VCCOA_5") (pintype "input"))
    )
    (net (code "7") (name "P3V3AUX") (class "Default")
      (node (ref "C79") (pin "1") (pinfunction "1_1") (pintype "input"))
      (node (ref "C88") (pin "1") (pinfunction "1_1") (pintype "input"))
      (node (ref "CEMX16_GOLD1") (pin "B10") (pinfunction "3V3AUX_B10") (pintype "output"))
      (node (ref "CN4") (pin "B10") (pinfunction "+3.3Vaux_B10") (pintype "output"))
      (node (ref "CN5") (pin "B10") (pinfunction "+3.3Vaux_B10") (pintype "output"))
    )
    (net (code "8") (name "P3V3_1") (class "Default")
      (node (ref "C45") (pin "1") (pinfunction "1_1") (pintype "input"))
      (node (ref "C46") (pin "1") (pinfunction "1_1") (pintype "input"))
      (node (ref "C77") (pin "1") (pinfunction "1_1") (pintype "input"))
      (node (ref "C78") (pin "1") (pinfunction "1_1") (pintype "input"))
      (node (ref "C82") (pin "1") (pinfunction "1_1") (pintype "input"))
      (node (ref "C83") (pin "1") (pinfunction "1_1") (pintype "input"))
      (node (ref "C86") (pin "1") (pinfunction "1_1") (pintype "input"))
      (node (ref "C87") (pin "1") (pinfunction "1_1") (pintype "input"))
      (node (ref "CEMX16_GOLD1") (pin "A10") (pinfunction "3V3_2_A10") (pintype "output"))
      (node (ref "CEMX16_GOLD1") (pin "A9") (pinfunction "3V3_1_A9") (pintype "output"))
      (node (ref "CEMX16_GOLD1") (pin "B8") (pinfunction "3V3_3_B8") (pintype "output"))
      (node (ref "CN4") (pin "A10") (pinfunction "+3.3V_A10") (pintype "output"))
      (node (ref "CN4") (pin "A9") (pinfunction "+3.3V_A9") (pintype "output"))
      (node (ref "CN4") (pin "B8") (pinfunction "+3.3V_B8") (pintype "output"))
      (node (ref "CN5") (pin "A10") (pinfunction "+3.3V_A10") (pintype "output"))
      (node (ref "CN5") (pin "A9") (pinfunction "+3.3V_A9") (pintype "output"))
      (node (ref "CN5") (pin "B8") (pinfunction "+3.3V_B8") (pintype "output"))
      (node (ref "L3") (pin "2") (pinfunction "2_2") (pintype "input"))
    )
    (net (code "9") (name "P12V") (class "Default")
      (node (ref "C40") (pin "1") (pinfunction "1_1") (pintype "input"))
      (node (ref "C41") (pin "1") (pinfunction "1_1") (pintype "input"))
      (node (ref "C80") (pin "1") (pinfunction "1_1") (pintype "input"))
      (node (ref "C81") (pin "1") (pinfunction "1_1") (pintype "input"))
      (node (ref "C84") (pin "1") (pinfunction "1_1") (pintype "input"))
      (node (ref "C85") (pin "1") (pinfunction "1_1") (pintype "input"))
      (node (ref "CEMX16_GOLD1") (pin "A2") (pinfunction "12V_1_A2") (pintype "output"))
      (node (ref "CEMX16_GOLD1") (pin "A3") (pinfunction "12V_2_A3") (pintype "output"))
      (node (ref "CEMX16_GOLD1") (pin "B1") (pinfunction "12V_3_B1") (pintype "output"))
      (node (ref "CEMX16_GOLD1") (pin "B2") (pinfunction "12V_4_B2") (pintype "output"))
      (node (ref "CEMX16_GOLD1") (pin "B3") (pinfunction "RSVD1_B3") (pintype "output"))
      (node (ref "CN4") (pin "A2") (pinfunction "+12V_A2") (pintype "output"))
      (node (ref "CN4") (pin "A3") (pinfunction "+12V_A3") (pintype "output"))
      (node (ref "CN4") (pin "B1") (pinfunction "+12V_B1") (pintype "output"))
      (node (ref "CN4") (pin "B2") (pinfunction "+12V_B2") (pintype "output"))
      (node (ref "CN4") (pin "B3") (pinfunction "+12V_B3") (pintype "output"))
      (node (ref "CN5") (pin "A2") (pinfunction "+12V_A2") (pintype "output"))
      (node (ref "CN5") (pin "A3") (pinfunction "+12V_A3") (pintype "output"))
      (node (ref "CN5") (pin "B1") (pinfunction "+12V_B1") (pintype "output"))
      (node (ref "CN5") (pin "B2") (pinfunction "+12V_B2") (pintype "output"))
      (node (ref "CN5") (pin "B3") (pinfunction "+12V_B3") (pintype "output"))
    )
    (net (code "10") (name "PE0_A0+") (class "Default")
      (node (ref "CEMX16_GOLD1") (pin "A16") (pinfunction "HSIP0+_A16") (pintype "input"))
      (node (ref "CN4") (pin "A16") (pinfunction "PETp0_A16") (pintype "input"))
    )
    (net (code "11") (name "PE0_A0-") (class "Default")
      (node (ref "CEMX16_GOLD1") (pin "A17") (pinfunction "HDIP0-_A17") (pintype "input"))
      (node (ref "CN4") (pin "A17") (pinfunction "PETn0_A17") (pintype "input"))
    )
    (net (code "12") (name "PE0_A1+") (class "Default")
      (node (ref "CEMX16_GOLD1") (pin "A21") (pinfunction "HSIP1+_A21") (pintype "input"))
      (node (ref "CN4") (pin "A21") (pinfunction "PETp1_A21") (pintype "input"))
    )
    (net (code "13") (name "PE0_A1-") (class "Default")
      (node (ref "CEMX16_GOLD1") (pin "A22") (pinfunction "HSIP1-_A22") (pintype "input"))
      (node (ref "CN4") (pin "A22") (pinfunction "PETn1_A22") (pintype "input"))
    )
    (net (code "14") (name "PE0_A2+") (class "Default")
      (node (ref "CEMX16_GOLD1") (pin "A25") (pinfunction "HSIP2+_A25") (pintype "input"))
      (node (ref "CN4") (pin "A25") (pinfunction "PETp2_A25") (pintype "input"))
    )
    (net (code "15") (name "PE0_A2-") (class "Default")
      (node (ref "CEMX16_GOLD1") (pin "A26") (pinfunction "HSIP2-_A26") (pintype "input"))
      (node (ref "CN4") (pin "A26") (pinfunction "PETn2_A26") (pintype "input"))
    )
    (net (code "16") (name "PE0_A3+") (class "Default")
      (node (ref "CEMX16_GOLD1") (pin "A29") (pinfunction "HSIP3+_A29") (pintype "input"))
      (node (ref "CN4") (pin "A29") (pinfunction "PETp3_A29") (pintype "input"))
    )
    (net (code "17") (name "PE0_A3-") (class "Default")
      (node (ref "CEMX16_GOLD1") (pin "A30") (pinfunction "HSIP3-_A30") (pintype "input"))
      (node (ref "CN4") (pin "A30") (pinfunction "PETn3_A30") (pintype "input"))
    )
    (net (code "18") (name "PE0_A4+") (class "Default")
      (node (ref "CEMX16_GOLD1") (pin "A35") (pinfunction "HSIP4+_A35") (pintype "input"))
      (node (ref "CN4") (pin "A35") (pinfunction "PETp4_A35") (pintype "input"))
    )
    (net (code "19") (name "PE0_A4-") (class "Default")
      (node (ref "CEMX16_GOLD1") (pin "A36") (pinfunction "HSIP4-_A36") (pintype "input"))
      (node (ref "CN4") (pin "A36") (pinfunction "PETn4_A36") (pintype "input"))
    )
    (net (code "20") (name "PE0_A5+") (class "Default")
      (node (ref "CEMX16_GOLD1") (pin "A39") (pinfunction "HSIP5+_A39") (pintype "input"))
      (node (ref "CN4") (pin "A39") (pinfunction "PETp5_A39") (pintype "input"))
    )
    (net (code "21") (name "PE0_A5-") (class "Default")
      (node (ref "CEMX16_GOLD1") (pin "A40") (pinfunction "HSIP5-_A40") (pintype "input"))
      (node (ref "CN4") (pin "A40") (pinfunction "PETn5_A40") (pintype "input"))
    )
    (net (code "22") (name "PE0_A6+") (class "Default")
      (node (ref "CEMX16_GOLD1") (pin "A43") (pinfunction "HSIP6+_A43") (pintype "input"))
      (node (ref "CN4") (pin "A43") (pinfunction "PETp6_A43") (pintype "input"))
    )
    (net (code "23") (name "PE0_A6-") (class "Default")
      (node (ref "CEMX16_GOLD1") (pin "A44") (pinfunction "HSIP6-_A44") (pintype "input"))
      (node (ref "CN4") (pin "A44") (pinfunction "PETn6_A44") (pintype "input"))
    )
    (net (code "24") (name "PE0_A7+") (class "Default")
      (node (ref "CEMX16_GOLD1") (pin "A47") (pinfunction "HSIP7+_A47") (pintype "input"))
      (node (ref "CN4") (pin "A47") (pinfunction "PETp7_A47") (pintype "input"))
    )
    (net (code "25") (name "PE0_A7-") (class "Default")
      (node (ref "CEMX16_GOLD1") (pin "A48") (pinfunction "HSIP7-_A48") (pintype "input"))
      (node (ref "CN4") (pin "A48") (pinfunction "PETn7_A48") (pintype "input"))
    )
    (net (code "26") (name "PE0_B0+") (class "Default")
      (node (ref "CEMX16_GOLD1") (pin "B14") (pinfunction "HSOP0+_B14") (pintype "output"))
      (node (ref "CN4") (pin "B14") (pinfunction "PERp0_B14") (pintype "output"))
    )
    (net (code "27") (name "PE0_B0-") (class "Default")
      (node (ref "CEMX16_GOLD1") (pin "B15") (pinfunction "HSOP0-_B15") (pintype "output"))
      (node (ref "CN4") (pin "B15") (pinfunction "PERn0_B15") (pintype "output"))
    )
    (net (code "28") (name "PE0_B1+") (class "Default")
      (node (ref "CEMX16_GOLD1") (pin "B19") (pinfunction "HSOP1+_B19") (pintype "output"))
      (node (ref "CN4") (pin "B19") (pinfunction "PERp1_B19") (pintype "output"))
    )
    (net (code "29") (name "PE0_B1-") (class "Default")
      (node (ref "CEMX16_GOLD1") (pin "B20") (pinfunction "HSOP1-_B20") (pintype "output"))
      (node (ref "CN4") (pin "B20") (pinfunction "PERn1_B20") (pintype "output"))
    )
    (net (code "30") (name "PE0_B2+") (class "Default")
      (node (ref "CEMX16_GOLD1") (pin "B23") (pinfunction "HSOP2+_B23") (pintype "output"))
      (node (ref "CN4") (pin "B23") (pinfunction "PERp2_B23") (pintype "output"))
    )
    (net (code "31") (name "PE0_B2-") (class "Default")
      (node (ref "CEMX16_GOLD1") (pin "B24") (pinfunction "HSOP2-_B24") (pintype "output"))
      (node (ref "CN4") (pin "B24") (pinfunction "PERn2_B24") (pintype "output"))
    )
    (net (code "32") (name "PE0_B3+") (class "Default")
      (node (ref "CEMX16_GOLD1") (pin "B27") (pinfunction "HSOP3+_B27") (pintype "output"))
      (node (ref "CN4") (pin "B27") (pinfunction "PERp3_B27") (pintype "output"))
    )
    (net (code "33") (name "PE0_B3-") (class "Default")
      (node (ref "CEMX16_GOLD1") (pin "B28") (pinfunction "HSOP3-_B28") (pintype "output"))
      (node (ref "CN4") (pin "B28") (pinfunction "PERn3_B28") (pintype "output"))
    )
    (net (code "34") (name "PE0_B4+") (class "Default")
      (node (ref "CEMX16_GOLD1") (pin "B33") (pinfunction "HSOP4+_B33") (pintype "output"))
      (node (ref "CN4") (pin "B33") (pinfunction "PERp4_B33") (pintype "output"))
    )
    (net (code "35") (name "PE0_B4-") (class "Default")
      (node (ref "CEMX16_GOLD1") (pin "B34") (pinfunction "HSOP4-_B34") (pintype "output"))
      (node (ref "CN4") (pin "B34") (pinfunction "PERn4_B34") (pintype "output"))
    )
    (net (code "36") (name "PE0_B5+") (class "Default")
      (node (ref "CEMX16_GOLD1") (pin "B37") (pinfunction "HSOP5+_B37") (pintype "output"))
      (node (ref "CN4") (pin "B37") (pinfunction "PERp5_B37") (pintype "output"))
    )
    (net (code "37") (name "PE0_B5-") (class "Default")
      (node (ref "CEMX16_GOLD1") (pin "B38") (pinfunction "HSOP5-_B38") (pintype "output"))
      (node (ref "CN4") (pin "B38") (pinfunction "PERn5_B38") (pintype "output"))
    )
    (net (code "38") (name "PE0_B6+") (class "Default")
      (node (ref "CEMX16_GOLD1") (pin "B41") (pinfunction "HSOP6+_B41") (pintype "output"))
      (node (ref "CN4") (pin "B41") (pinfunction "PERp6_B41") (pintype "output"))
    )
    (net (code "39") (name "PE0_B6-") (class "Default")
      (node (ref "CEMX16_GOLD1") (pin "B42") (pinfunction "HSOP6-_B42") (pintype "output"))
      (node (ref "CN4") (pin "B42") (pinfunction "PERn6_B42") (pintype "output"))
    )
    (net (code "40") (name "PE0_B7+") (class "Default")
      (node (ref "CEMX16_GOLD1") (pin "B45") (pinfunction "HSOP7+_B45") (pintype "output"))
      (node (ref "CN4") (pin "B45") (pinfunction "PERp7_B45") (pintype "output"))
    )
    (net (code "41") (name "PE0_B7-") (class "Default")
      (node (ref "CEMX16_GOLD1") (pin "B46") (pinfunction "HSOP7-_B46") (pintype "output"))
      (node (ref "CN4") (pin "B46") (pinfunction "PERn7_B46") (pintype "output"))
    )
    (net (code "42") (name "PE0_CLK+") (class "Default")
      (node (ref "CN4") (pin "A13") (pinfunction "REFCLKp_A13") (pintype "output"))
      (node (ref "R39") (pin "2") (pinfunction "2_2") (pintype "input"))
      (node (ref "R47") (pin "2") (pinfunction "2_2") (pintype "input"))
    )
    (net (code "43") (name "PE0_CLK-") (class "Default")
      (node (ref "CN4") (pin "A14") (pinfunction "REFCLKn_A14") (pintype "output"))
      (node (ref "R40") (pin "2") (pinfunction "2_2") (pintype "input"))
      (node (ref "R48") (pin "2") (pinfunction "2_2") (pintype "input"))
    )
    (net (code "44") (name "PE1_A0+") (class "Default")
      (node (ref "CEMX16_GOLD1") (pin "A52") (pinfunction "HSIP8+_A52") (pintype "input"))
      (node (ref "CN5") (pin "A16") (pinfunction "PETp0_A16") (pintype "input"))
    )
    (net (code "45") (name "PE1_A0-") (class "Default")
      (node (ref "CEMX16_GOLD1") (pin "A53") (pinfunction "HSIP8-_A53") (pintype "input"))
      (node (ref "CN5") (pin "A17") (pinfunction "PETn0_A17") (pintype "input"))
    )
    (net (code "46") (name "PE1_A1+") (class "Default")
      (node (ref "CEMX16_GOLD1") (pin "A56") (pinfunction "HSIP9+_A56") (pintype "input"))
      (node (ref "CN5") (pin "A21") (pinfunction "PETp1_A21") (pintype "input"))
    )
    (net (code "47") (name "PE1_A1-") (class "Default")
      (node (ref "CEMX16_GOLD1") (pin "A57") (pinfunction "HSIP9-_A57") (pintype "input"))
      (node (ref "CN5") (pin "A22") (pinfunction "PETn1_A22") (pintype "input"))
    )
    (net (code "48") (name "PE1_A2+") (class "Default")
      (node (ref "CEMX16_GOLD1") (pin "A60") (pinfunction "HSIP10+_A60") (pintype "input"))
      (node (ref "CN5") (pin "A25") (pinfunction "PETp2_A25") (pintype "input"))
    )
    (net (code "49") (name "PE1_A2-") (class "Default")
      (node (ref "CEMX16_GOLD1") (pin "A61") (pinfunction "HSIP10-_A61") (pintype "input"))
      (node (ref "CN5") (pin "A26") (pinfunction "PETn2_A26") (pintype "input"))
    )
    (net (code "50") (name "PE1_A3+") (class "Default")
      (node (ref "CEMX16_GOLD1") (pin "A64") (pinfunction "HSIP11+_A64") (pintype "input"))
      (node (ref "CN5") (pin "A29") (pinfunction "PETp3_A29") (pintype "input"))
    )
    (net (code "51") (name "PE1_A3-") (class "Default")
      (node (ref "CEMX16_GOLD1") (pin "A65") (pinfunction "HSIP11-_A65") (pintype "input"))
      (node (ref "CN5") (pin "A30") (pinfunction "PETn3_A30") (pintype "input"))
    )
    (net (code "52") (name "PE1_A4+") (class "Default")
      (node (ref "CEMX16_GOLD1") (pin "A68") (pinfunction "HSIP12+_A68") (pintype "input"))
      (node (ref "CN5") (pin "A35") (pinfunction "PETp4_A35") (pintype "input"))
    )
    (net (code "53") (name "PE1_A4-") (class "Default")
      (node (ref "CEMX16_GOLD1") (pin "A69") (pinfunction "HSIP12-_A69") (pintype "input"))
      (node (ref "CN5") (pin "A36") (pinfunction "PETn4_A36") (pintype "input"))
    )
    (net (code "54") (name "PE1_A5+") (class "Default")
      (node (ref "CEMX16_GOLD1") (pin "A72") (pinfunction "HSIP13+_A72") (pintype "input"))
      (node (ref "CN5") (pin "A39") (pinfunction "PETp5_A39") (pintype "input"))
    )
    (net (code "55") (name "PE1_A5-") (class "Default")
      (node (ref "CEMX16_GOLD1") (pin "A73") (pinfunction "HSIP13-_A73") (pintype "input"))
      (node (ref "CN5") (pin "A40") (pinfunction "PETn5_A40") (pintype "input"))
    )
    (net (code "56") (name "PE1_A6+") (class "Default")
      (node (ref "CEMX16_GOLD1") (pin "A76") (pinfunction "HSIP14+_A76") (pintype "input"))
      (node (ref "CN5") (pin "A43") (pinfunction "PETp6_A43") (pintype "input"))
    )
    (net (code "57") (name "PE1_A6-") (class "Default")
      (node (ref "CEMX16_GOLD1") (pin "A77") (pinfunction "HSIP14-_A77") (pintype "input"))
      (node (ref "CN5") (pin "A44") (pinfunction "PETn6_A44") (pintype "input"))
    )
    (net (code "58") (name "PE1_A7+") (class "Default")
      (node (ref "CEMX16_GOLD1") (pin "A80") (pinfunction "HSIP15+_A80") (pintype "input"))
      (node (ref "CN5") (pin "A47") (pinfunction "PETp7_A47") (pintype "input"))
    )
    (net (code "59") (name "PE1_A7-") (class "Default")
      (node (ref "CEMX16_GOLD1") (pin "A81") (pinfunction "HSIP15-_A81") (pintype "input"))
      (node (ref "CN5") (pin "A48") (pinfunction "PETn7_A48") (pintype "input"))
    )
    (net (code "60") (name "PE1_B0+") (class "Default")
      (node (ref "CEMX16_GOLD1") (pin "B50") (pinfunction "HSOP8+_B50") (pintype "output"))
      (node (ref "CN5") (pin "B14") (pinfunction "PERp0_B14") (pintype "output"))
    )
    (net (code "61") (name "PE1_B0-") (class "Default")
      (node (ref "CEMX16_GOLD1") (pin "B51") (pinfunction "HSOP8-_B51") (pintype "output"))
      (node (ref "CN5") (pin "B15") (pinfunction "PERn0_B15") (pintype "output"))
    )
    (net (code "62") (name "PE1_B1+") (class "Default")
      (node (ref "CEMX16_GOLD1") (pin "B54") (pinfunction "HSOP9+_B54") (pintype "output"))
      (node (ref "CN5") (pin "B19") (pinfunction "PERp1_B19") (pintype "output"))
    )
    (net (code "63") (name "PE1_B1-") (class "Default")
      (node (ref "CEMX16_GOLD1") (pin "B55") (pinfunction "HSOP9-_B55") (pintype "output"))
      (node (ref "CN5") (pin "B20") (pinfunction "PERn1_B20") (pintype "output"))
    )
    (net (code "64") (name "PE1_B2+") (class "Default")
      (node (ref "CEMX16_GOLD1") (pin "B58") (pinfunction "HSOP10+_B58") (pintype "output"))
      (node (ref "CN5") (pin "B23") (pinfunction "PERp2_B23") (pintype "output"))
    )
    (net (code "65") (name "PE1_B2-") (class "Default")
      (node (ref "CEMX16_GOLD1") (pin "B59") (pinfunction "HSOP10-_B59") (pintype "output"))
      (node (ref "CN5") (pin "B24") (pinfunction "PERn2_B24") (pintype "output"))
    )
    (net (code "66") (name "PE1_B3+") (class "Default")
      (node (ref "CEMX16_GOLD1") (pin "B62") (pinfunction "HSOP11+_B62") (pintype "output"))
      (node (ref "CN5") (pin "B27") (pinfunction "PERp3_B27") (pintype "output"))
    )
    (net (code "67") (name "PE1_B3-") (class "Default")
      (node (ref "CEMX16_GOLD1") (pin "B63") (pinfunction "HSOP11-_B63") (pintype "output"))
      (node (ref "CN5") (pin "B28") (pinfunction "PERn3_B28") (pintype "output"))
    )
    (net (code "68") (name "PE1_B4+") (class "Default")
      (node (ref "CEMX16_GOLD1") (pin "B66") (pinfunction "HSOP12+_B66") (pintype "output"))
      (node (ref "CN5") (pin "B33") (pinfunction "PERp4_B33") (pintype "output"))
    )
    (net (code "69") (name "PE1_B4-") (class "Default")
      (node (ref "CEMX16_GOLD1") (pin "B67") (pinfunction "HSOP12-_B67") (pintype "output"))
      (node (ref "CN5") (pin "B34") (pinfunction "PERn4_B34") (pintype "output"))
    )
    (net (code "70") (name "PE1_B5+") (class "Default")
      (node (ref "CEMX16_GOLD1") (pin "B70") (pinfunction "HSOP13+_B70") (pintype "output"))
      (node (ref "CN5") (pin "B37") (pinfunction "PERp5_B37") (pintype "output"))
    )
    (net (code "71") (name "PE1_B5-") (class "Default")
      (node (ref "CEMX16_GOLD1") (pin "B71") (pinfunction "HSOP13-_B71") (pintype "output"))
      (node (ref "CN5") (pin "B38") (pinfunction "PERn5_B38") (pintype "output"))
    )
    (net (code "72") (name "PE1_B6+") (class "Default")
      (node (ref "CEMX16_GOLD1") (pin "B74") (pinfunction "HSOP14+_B74") (pintype "output"))
      (node (ref "CN5") (pin "B41") (pinfunction "PERp6_B41") (pintype "output"))
    )
    (net (code "73") (name "PE1_B6-") (class "Default")
      (node (ref "CEMX16_GOLD1") (pin "B75") (pinfunction "HSOP14-_B75") (pintype "output"))
      (node (ref "CN5") (pin "B42") (pinfunction "PERn6_B42") (pintype "output"))
    )
    (net (code "74") (name "PE1_B7+") (class "Default")
      (node (ref "CEMX16_GOLD1") (pin "B78") (pinfunction "HSOP15+_B78") (pintype "output"))
      (node (ref "CN5") (pin "B45") (pinfunction "PERp7_B45") (pintype "output"))
    )
    (net (code "75") (name "PE1_B7-") (class "Default")
      (node (ref "CEMX16_GOLD1") (pin "B79") (pinfunction "HSOP15-_B79") (pintype "output"))
      (node (ref "CN5") (pin "B46") (pinfunction "PERn7_B46") (pintype "output"))
    )
    (net (code "76") (name "PE1_CLK+") (class "Default")
      (node (ref "CN5") (pin "A13") (pinfunction "REFCLKp_A13") (pintype "output"))
      (node (ref "R37") (pin "2") (pinfunction "2_2") (pintype "input"))
      (node (ref "R45") (pin "2") (pinfunction "2_2") (pintype "input"))
    )
    (net (code "77") (name "PE1_CLK-") (class "Default")
      (node (ref "CN5") (pin "A14") (pinfunction "REFCLKn_A14") (pintype "output"))
      (node (ref "R38") (pin "2") (pinfunction "2_2") (pintype "input"))
      (node (ref "R46") (pin "2") (pinfunction "2_2") (pintype "input"))
    )
    (net (code "78") (name "PERST#") (class "Default")
      (node (ref "CEMX16_GOLD1") (pin "A11") (pinfunction "PERST#_A11") (pintype "output"))
      (node (ref "CN4") (pin "A11") (pinfunction "PERST#_A11") (pintype "output"))
      (node (ref "CN5") (pin "A11") (pinfunction "PERST#_A11") (pintype "output"))
    )
    (net (code "79") (name "REFCLK+") (class "Default")
      (node (ref "CEMX16_GOLD1") (pin "A13") (pinfunction "REFCLK+_A13") (pintype "output"))
      (node (ref "U1") (pin "14") (pinfunction "CLKin0_14") (pintype "input"))
    )
    (net (code "80") (name "REFCLK-") (class "Default")
      (node (ref "CEMX16_GOLD1") (pin "A14") (pinfunction "REFCLK-_A14") (pintype "output"))
      (node (ref "U1") (pin "15") (pinfunction "CLKin0*_15") (pintype "input"))
    )
    (net (code "81") (name "SMCLK") (class "Default")
      (node (ref "CEMX16_GOLD1") (pin "B5") (pinfunction "SMCLK_B5") (pintype "input"))
      (node (ref "CN4") (pin "B5") (pinfunction "SMBCLK_B5") (pintype "input"))
    )
    (net (code "82") (name "SMDAT") (class "Default")
      (node (ref "CEMX16_GOLD1") (pin "B6") (pinfunction "SMDAT_B6") (pintype "bidirectional"))
      (node (ref "CN4") (pin "B6") (pinfunction "SMBDAT_B6") (pintype "bidirectional"))
    )
    (net (code "83") (name "WAKE#") (class "Default")
      (node (ref "CEMX16_GOLD1") (pin "B11") (pinfunction "WAKE#_B11") (pintype "input"))
      (node (ref "CN4") (pin "B11") (pinfunction "WAKE#_B11") (pintype "input"))
      (node (ref "CN5") (pin "B11") (pinfunction "WAKE#_B11") (pintype "input"))
    )
    (net (code "84") (name "unconnected-(CEMX16_GOLD1-JTAG1-PadB9)") (class "Default")
      (node (ref "CEMX16_GOLD1") (pin "B9") (pinfunction "JTAG1_B9") (pintype "no_connect"))
    )
    (net (code "85") (name "unconnected-(CEMX16_GOLD1-JTAG2-PadA5)") (class "Default")
      (node (ref "CEMX16_GOLD1") (pin "A5") (pinfunction "JTAG2_A5") (pintype "no_connect"))
    )
    (net (code "86") (name "unconnected-(CEMX16_GOLD1-JTAG3-PadA6)") (class "Default")
      (node (ref "CEMX16_GOLD1") (pin "A6") (pinfunction "JTAG3_A6") (pintype "no_connect"))
    )
    (net (code "87") (name "unconnected-(CEMX16_GOLD1-JTAG4-PadA7)") (class "Default")
      (node (ref "CEMX16_GOLD1") (pin "A7") (pinfunction "JTAG4_A7") (pintype "no_connect"))
    )
    (net (code "88") (name "unconnected-(CEMX16_GOLD1-JTAG5-PadA8)") (class "Default")
      (node (ref "CEMX16_GOLD1") (pin "A8") (pinfunction "JTAG5_A8") (pintype "no_connect"))
    )
    (net (code "89") (name "unconnected-(CEMX16_GOLD1-RVSD2-PadB12)") (class "Default")
      (node (ref "CEMX16_GOLD1") (pin "B12") (pinfunction "RVSD2_B12") (pintype "no_connect"))
    )
    (net (code "90") (name "unconnected-(CEMX16_GOLD1-RVSD3-PadB30)") (class "Default")
      (node (ref "CEMX16_GOLD1") (pin "B30") (pinfunction "RVSD3_B30") (pintype "no_connect"))
    )
    (net (code "91") (name "unconnected-(CEMX16_GOLD1-RVSD4-PadB82)") (class "Default")
      (node (ref "CEMX16_GOLD1") (pin "B82") (pinfunction "RVSD4_B82") (pintype "no_connect"))
    )
    (net (code "92") (name "unconnected-(CEMX16_GOLD1-RVSD5-PadA19)") (class "Default")
      (node (ref "CEMX16_GOLD1") (pin "A19") (pinfunction "RVSD5_A19") (pintype "no_connect"))
    )
    (net (code "93") (name "unconnected-(CEMX16_GOLD1-RVSD6-PadA32)") (class "Default")
      (node (ref "CEMX16_GOLD1") (pin "A32") (pinfunction "RVSD6_A32") (pintype "no_connect"))
    )
    (net (code "94") (name "unconnected-(CEMX16_GOLD1-RVSD7-PadA33)") (class "Default")
      (node (ref "CEMX16_GOLD1") (pin "A33") (pinfunction "RVSD7_A33") (pintype "no_connect"))
    )
    (net (code "95") (name "unconnected-(CEMX16_GOLD1-RVSD8-PadA50)") (class "Default")
      (node (ref "CEMX16_GOLD1") (pin "A50") (pinfunction "RVSD8_A50") (pintype "no_connect"))
    )
    (net (code "96") (name "unconnected-(CN4-CLKREQ#-PadB12)") (class "Default")
      (node (ref "CN4") (pin "B12") (pinfunction "CLKREQ#_B12") (pintype "input+no_connect"))
    )
    (net (code "97") (name "unconnected-(CN4-JTAG1-PadB9)") (class "Default")
      (node (ref "CN4") (pin "B9") (pinfunction "JTAG1_B9") (pintype "input+no_connect"))
    )
    (net (code "98") (name "unconnected-(CN4-JTAG2-PadA5)") (class "Default")
      (node (ref "CN4") (pin "A5") (pinfunction "JTAG2_A5") (pintype "input+no_connect"))
    )
    (net (code "99") (name "unconnected-(CN4-JTAG3-PadA6)") (class "Default")
      (node (ref "CN4") (pin "A6") (pinfunction "JTAG3_A6") (pintype "input+no_connect"))
    )
    (net (code "100") (name "unconnected-(CN4-JTAG4-PadA7)") (class "Default")
      (node (ref "CN4") (pin "A7") (pinfunction "JTAG4_A7") (pintype "input+no_connect"))
    )
    (net (code "101") (name "unconnected-(CN4-JTAG5-PadA8)") (class "Default")
      (node (ref "CN4") (pin "A8") (pinfunction "JTAG5_A8") (pintype "input+no_connect"))
    )
    (net (code "102") (name "unconnected-(CN4-PWRBRK#-PadB30)") (class "Default")
      (node (ref "CN4") (pin "B30") (pinfunction "PWRBRK#_B30") (pintype "input+no_connect"))
    )
    (net (code "103") (name "unconnected-(CN4-RVSD-PadA19)") (class "Default")
      (node (ref "CN4") (pin "A19") (pinfunction "RVSD_A19") (pintype "input+no_connect"))
    )
    (net (code "104") (name "unconnected-(CN4-RVSD-PadA32)") (class "Default")
      (node (ref "CN4") (pin "A32") (pinfunction "RVSD_A32") (pintype "input+no_connect"))
    )
    (net (code "105") (name "unconnected-(CN4-RVSD-PadA33)") (class "Default")
      (node (ref "CN4") (pin "A33") (pinfunction "RVSD_A33") (pintype "input+no_connect"))
    )
    (net (code "106") (name "unconnected-(CN5-CLKREQ#-PadB12)") (class "Default")
      (node (ref "CN5") (pin "B12") (pinfunction "CLKREQ#_B12") (pintype "input+no_connect"))
    )
    (net (code "107") (name "unconnected-(CN5-JTAG1-PadB9)") (class "Default")
      (node (ref "CN5") (pin "B9") (pinfunction "JTAG1_B9") (pintype "input+no_connect"))
    )
    (net (code "108") (name "unconnected-(CN5-JTAG2-PadA5)") (class "Default")
      (node (ref "CN5") (pin "A5") (pinfunction "JTAG2_A5") (pintype "input+no_connect"))
    )
    (net (code "109") (name "unconnected-(CN5-JTAG3-PadA6)") (class "Default")
      (node (ref "CN5") (pin "A6") (pinfunction "JTAG3_A6") (pintype "input+no_connect"))
    )
    (net (code "110") (name "unconnected-(CN5-JTAG4-PadA7)") (class "Default")
      (node (ref "CN5") (pin "A7") (pinfunction "JTAG4_A7") (pintype "input+no_connect"))
    )
    (net (code "111") (name "unconnected-(CN5-JTAG5-PadA8)") (class "Default")
      (node (ref "CN5") (pin "A8") (pinfunction "JTAG5_A8") (pintype "input+no_connect"))
    )
    (net (code "112") (name "unconnected-(CN5-PWRBRK#-PadB30)") (class "Default")
      (node (ref "CN5") (pin "B30") (pinfunction "PWRBRK#_B30") (pintype "input+no_connect"))
    )
    (net (code "113") (name "unconnected-(CN5-RVSD-PadA19)") (class "Default")
      (node (ref "CN5") (pin "A19") (pinfunction "RVSD_A19") (pintype "input+no_connect"))
    )
    (net (code "114") (name "unconnected-(CN5-RVSD-PadA32)") (class "Default")
      (node (ref "CN5") (pin "A32") (pinfunction "RVSD_A32") (pintype "input+no_connect"))
    )
    (net (code "115") (name "unconnected-(CN5-RVSD-PadA33)") (class "Default")
      (node (ref "CN5") (pin "A33") (pinfunction "RVSD_A33") (pintype "input+no_connect"))
    )
    (net (code "116") (name "unconnected-(CN5-SMBCLK-PadB5)") (class "Default")
      (node (ref "CN5") (pin "B5") (pinfunction "SMBCLK_B5") (pintype "input+no_connect"))
    )
    (net (code "117") (name "unconnected-(CN5-SMBDAT-PadB6)") (class "Default")
      (node (ref "CN5") (pin "B6") (pinfunction "SMBDAT_B6") (pintype "bidirectional+no_connect"))
    )
    (net (code "118") (name "unconnected-(U1-CLKin1*-Pad26)") (class "Default")
      (node (ref "U1") (pin "26") (pinfunction "CLKin1*_26") (pintype "input+no_connect"))
    )
    (net (code "119") (name "unconnected-(U1-CLKin1-Pad27)") (class "Default")
      (node (ref "U1") (pin "27") (pinfunction "CLKin1_27") (pintype "input+no_connect"))
    )
    (net (code "120") (name "unconnected-(U1-CLKoutA0*-Pad4)") (class "Default")
      (node (ref "U1") (pin "4") (pinfunction "CLKoutA0*_4") (pintype "input+no_connect"))
    )
    (net (code "121") (name "unconnected-(U1-CLKoutA0-Pad3)") (class "Default")
      (node (ref "U1") (pin "3") (pinfunction "CLKoutA0_3") (pintype "input+no_connect"))
    )
    (net (code "122") (name "unconnected-(U1-CLKoutA1*-Pad7)") (class "Default")
      (node (ref "U1") (pin "7") (pinfunction "CLKoutA1*_7") (pintype "input+no_connect"))
    )
    (net (code "123") (name "unconnected-(U1-CLKoutA1-Pad6)") (class "Default")
      (node (ref "U1") (pin "6") (pinfunction "CLKoutA1_6") (pintype "input+no_connect"))
    )
    (net (code "124") (name "unconnected-(U1-NC-Pad25)") (class "Default")
      (node (ref "U1") (pin "25") (pinfunction "NC_25") (pintype "input+no_connect"))
    )
    (net (code "125") (name "unconnected-(U1-OSCin-Pad11)") (class "Default")
      (node (ref "U1") (pin "11") (pinfunction "OSCin_11") (pintype "input+no_connect"))
    )
    (net (code "126") (name "unconnected-(U1-OSCout-Pad12)") (class "Default")
      (node (ref "U1") (pin "12") (pinfunction "OSCout_12") (pintype "input+no_connect"))
    )
    (net (code "127") (name "unconnected-(U1-REFout-Pad29)") (class "Default")
      (node (ref "U1") (pin "29") (pinfunction "REFout_29") (pintype "input+no_connect"))
    )
  )
)
